# SCH_FCPLCM-2v0_2024-09-18.net
KiCad netlist of a schematic drawn in EasyEDA
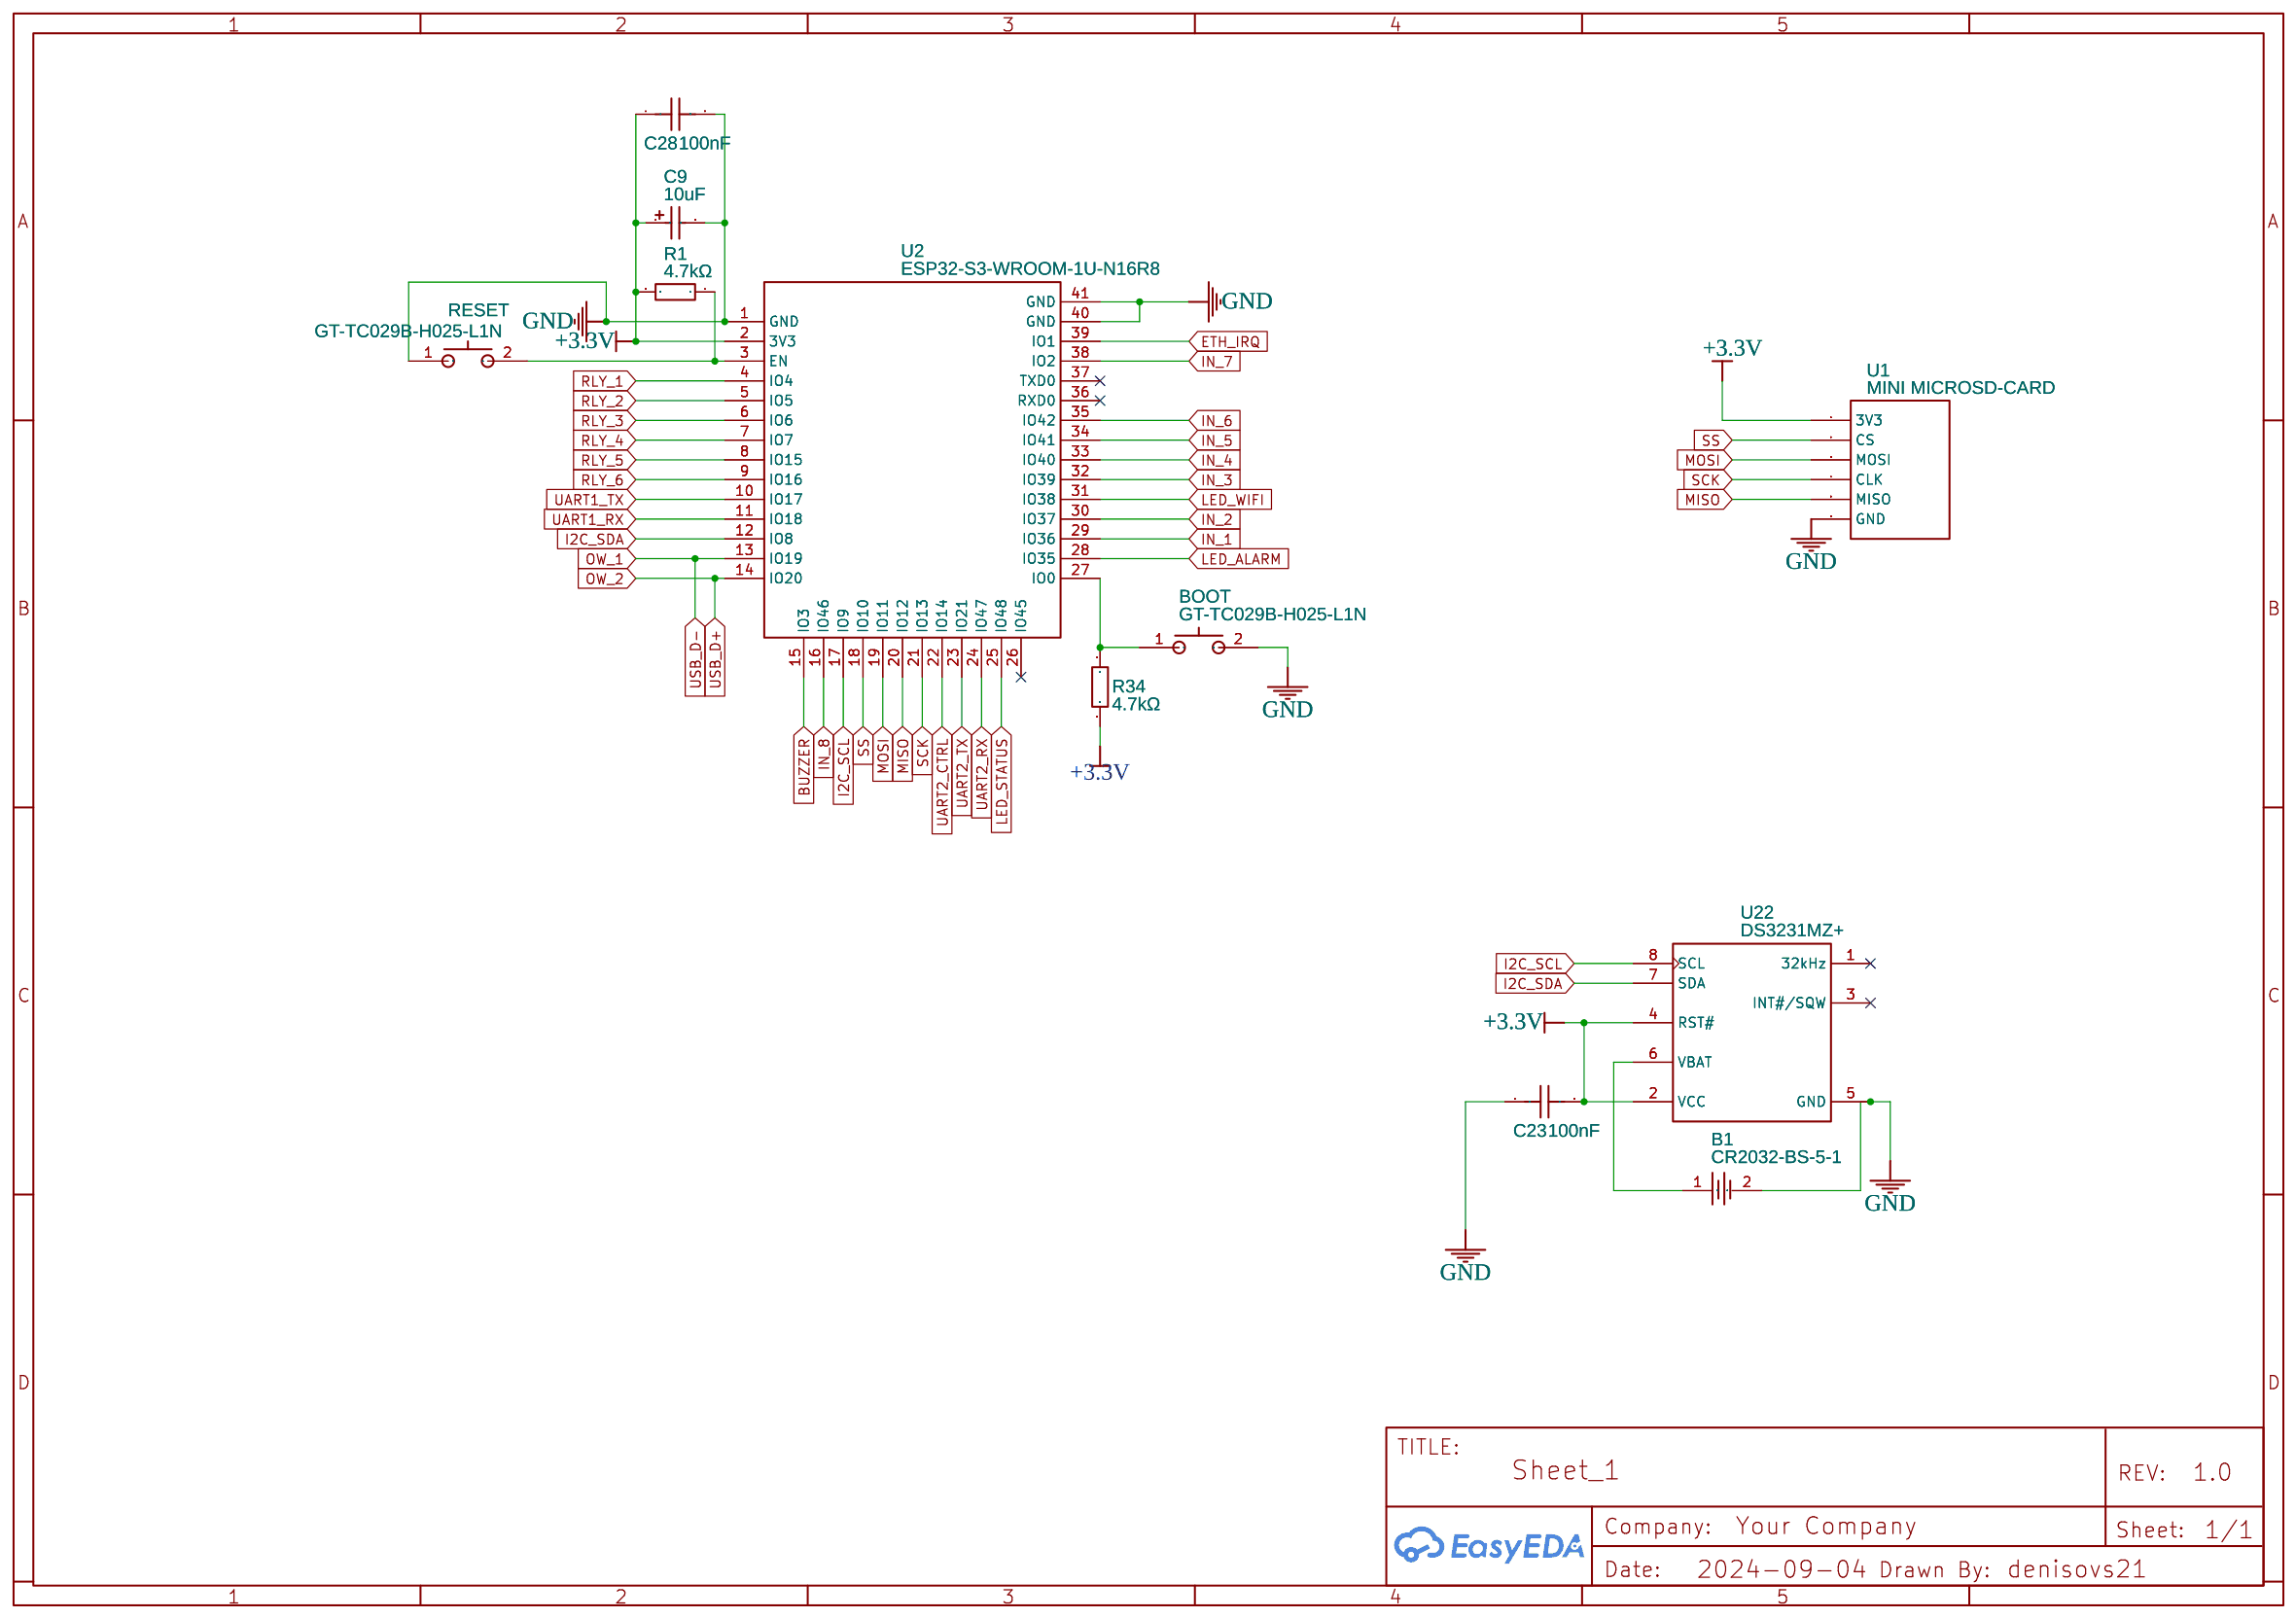
[diagram p0: CPU]
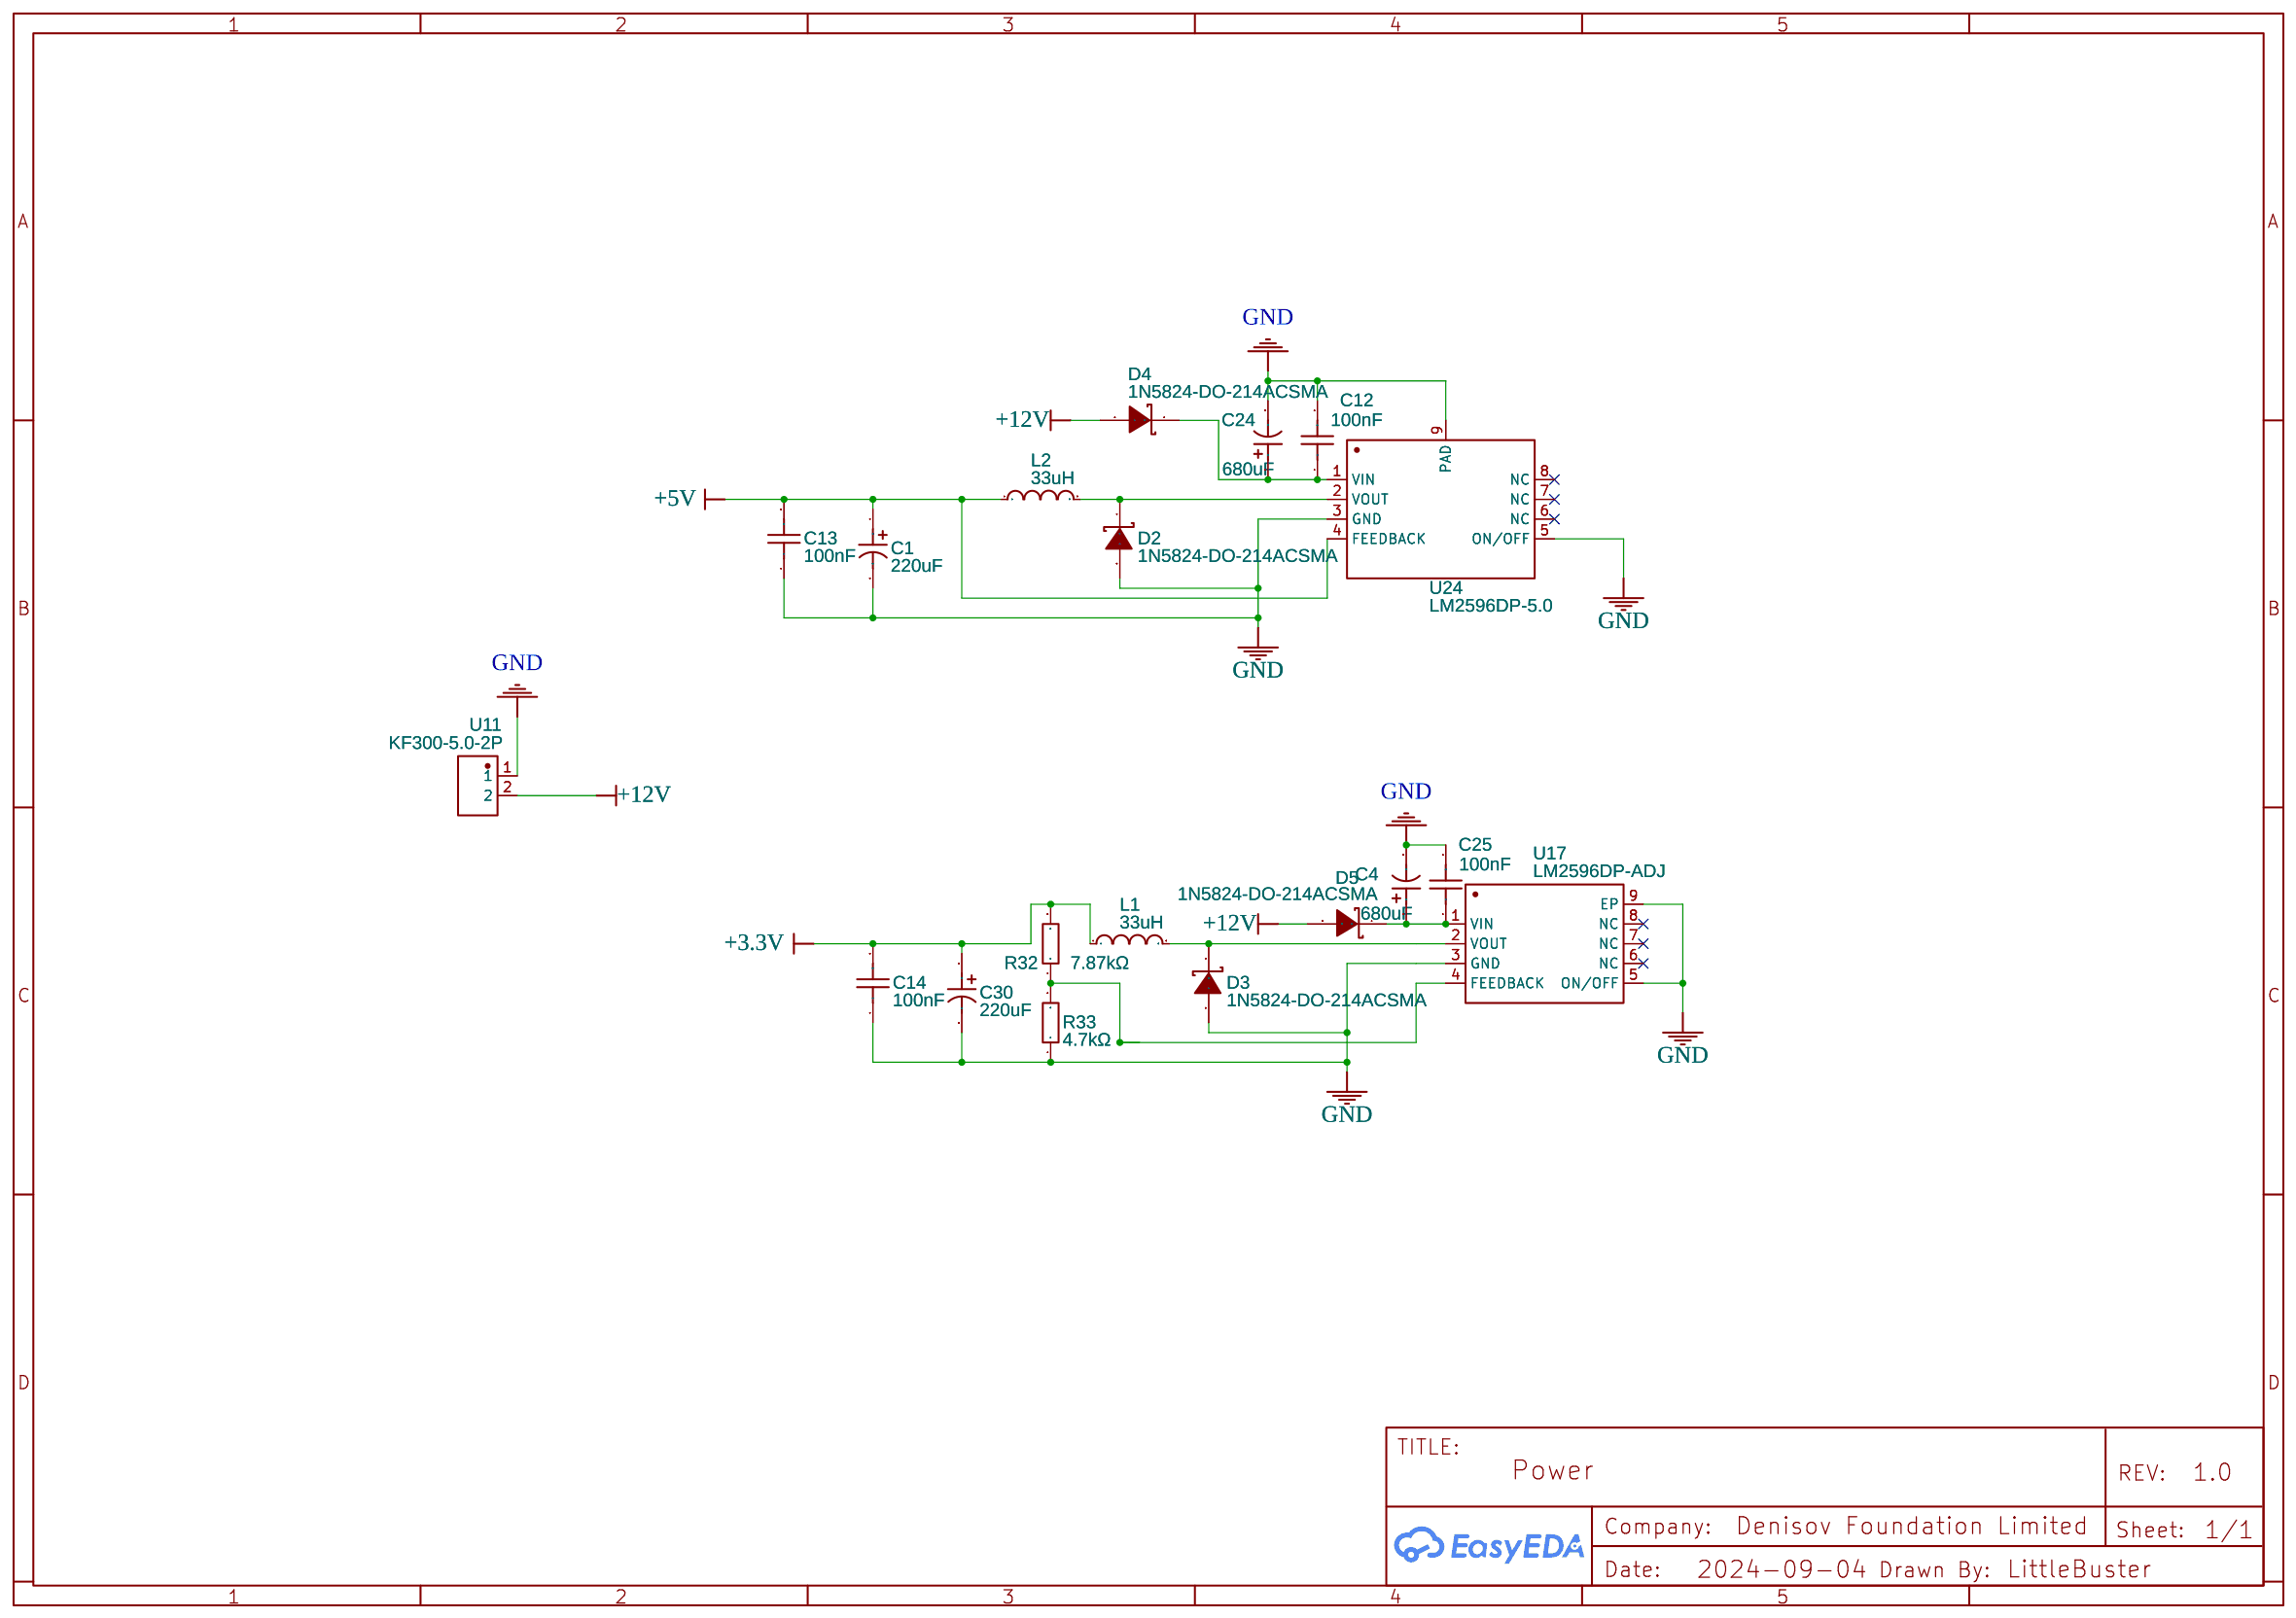
[diagram p1: Power]
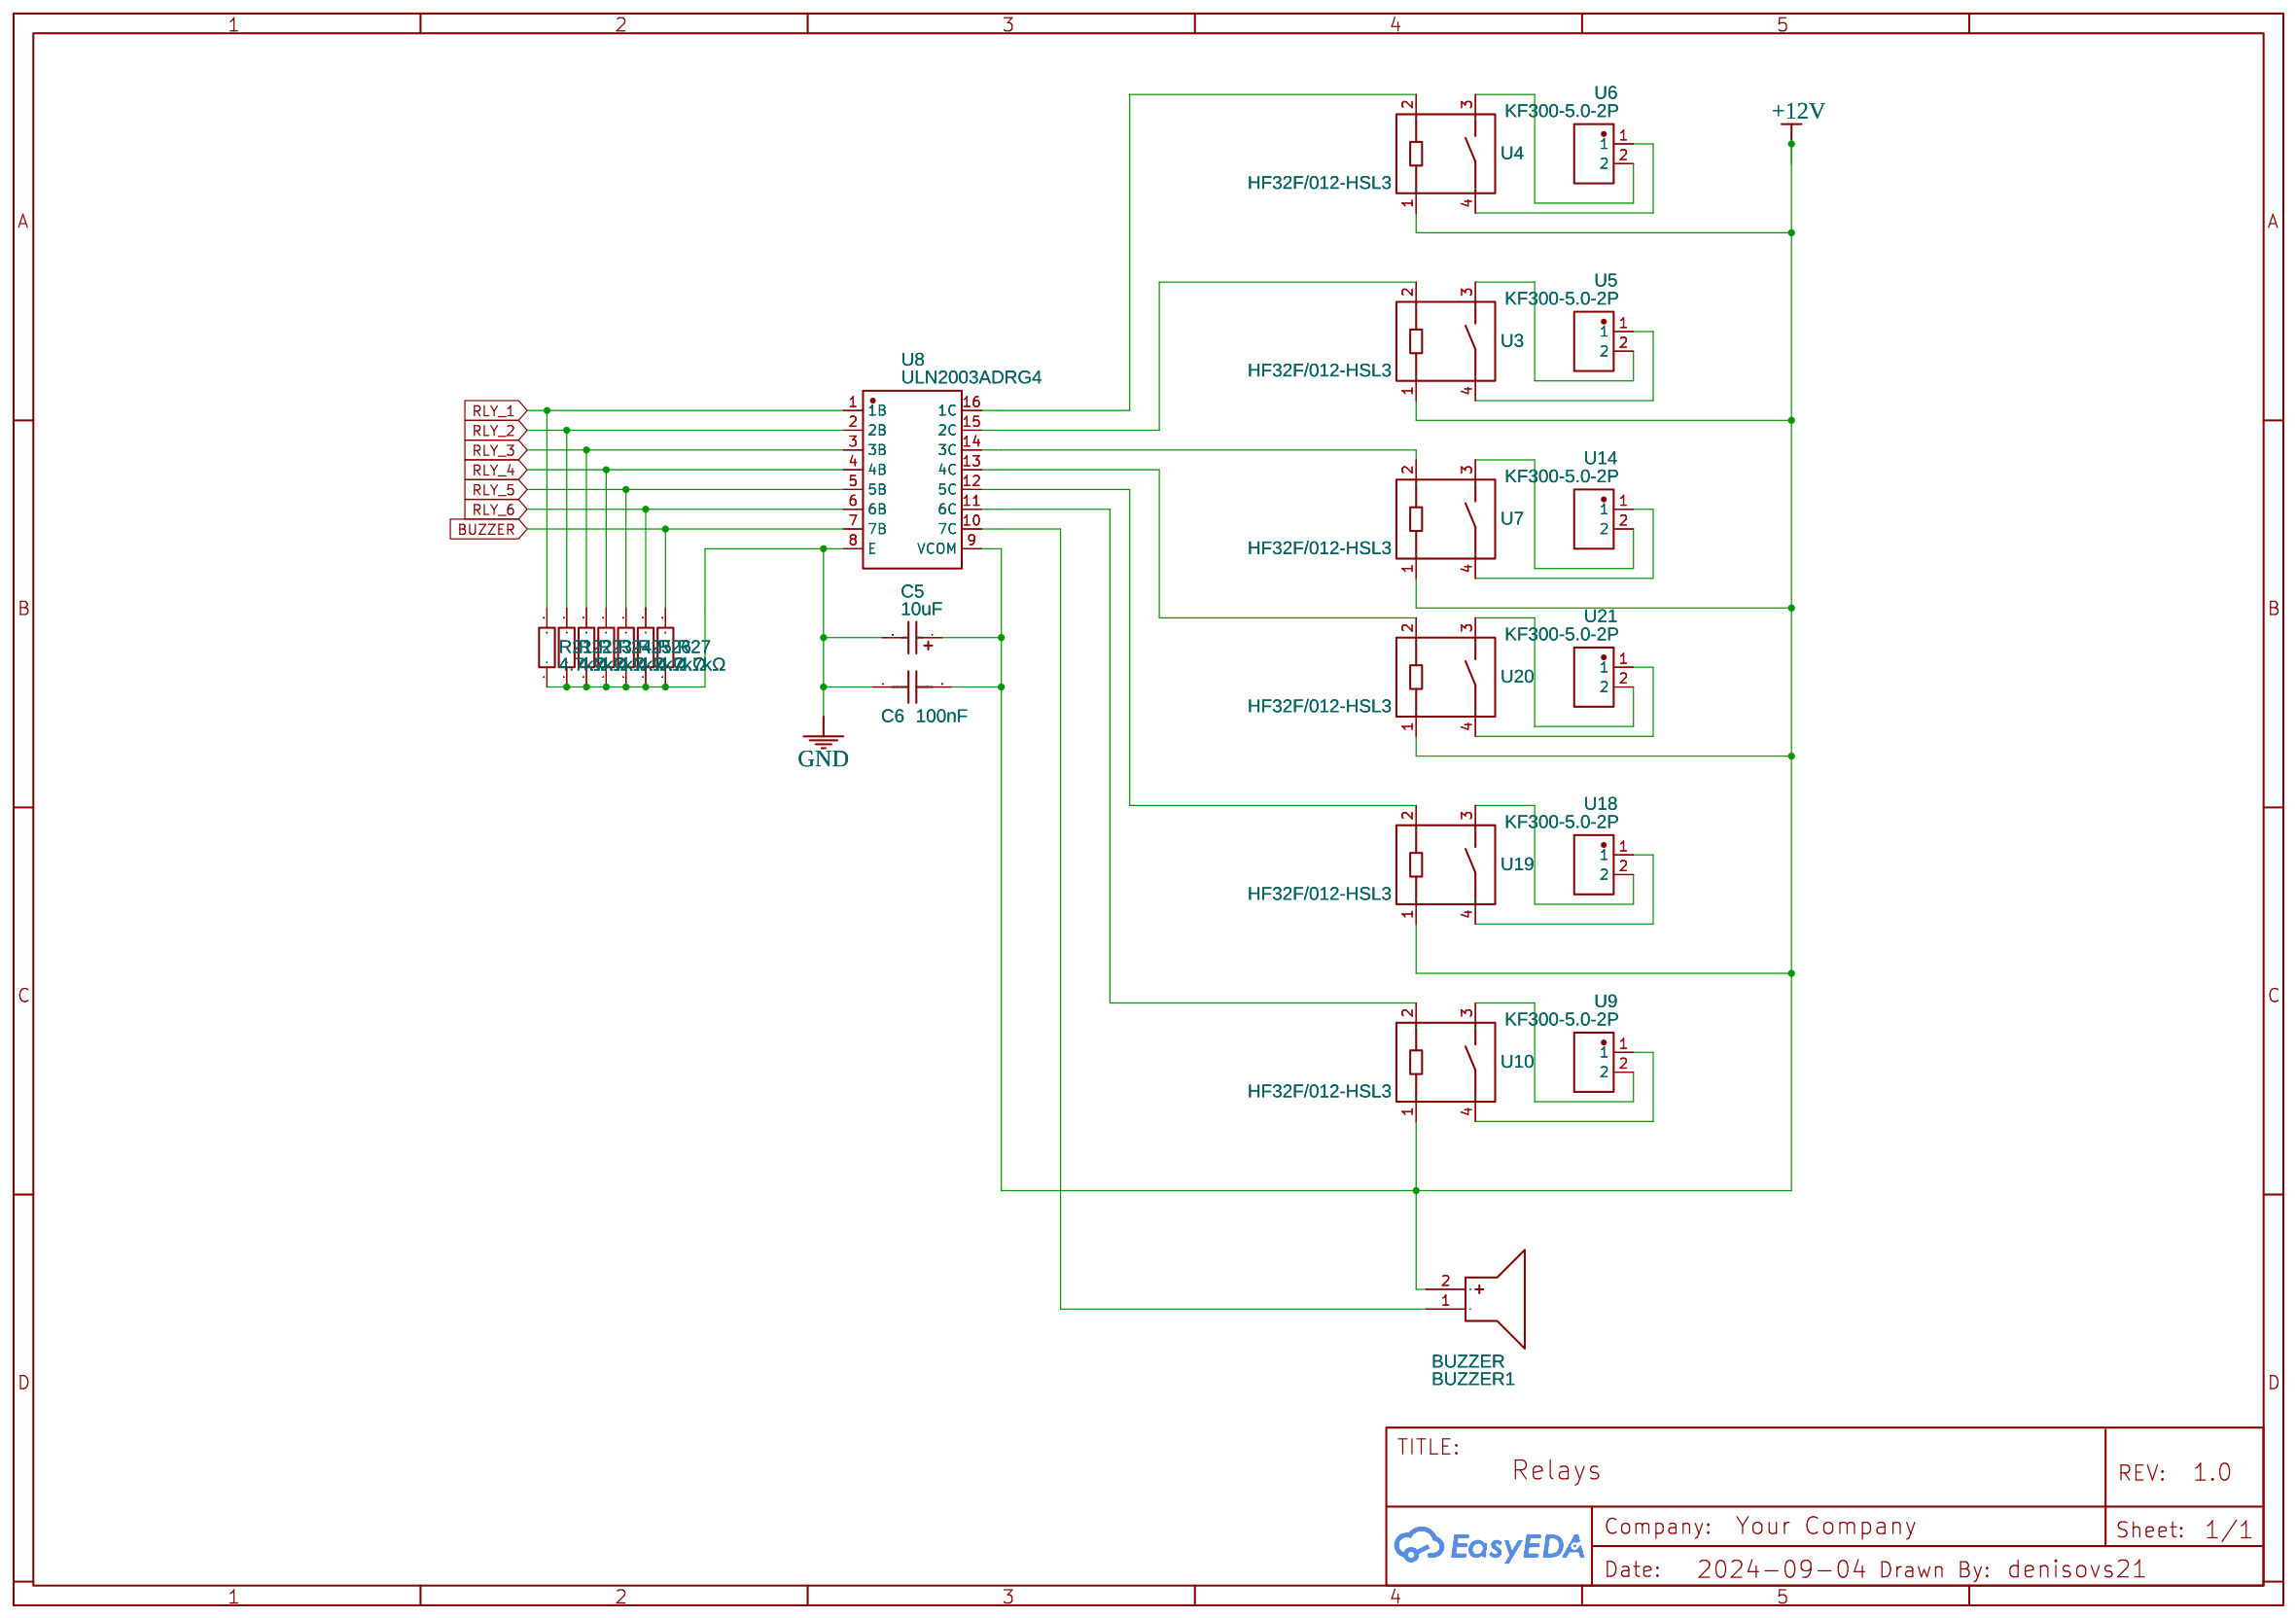
[diagram p2: Relays]
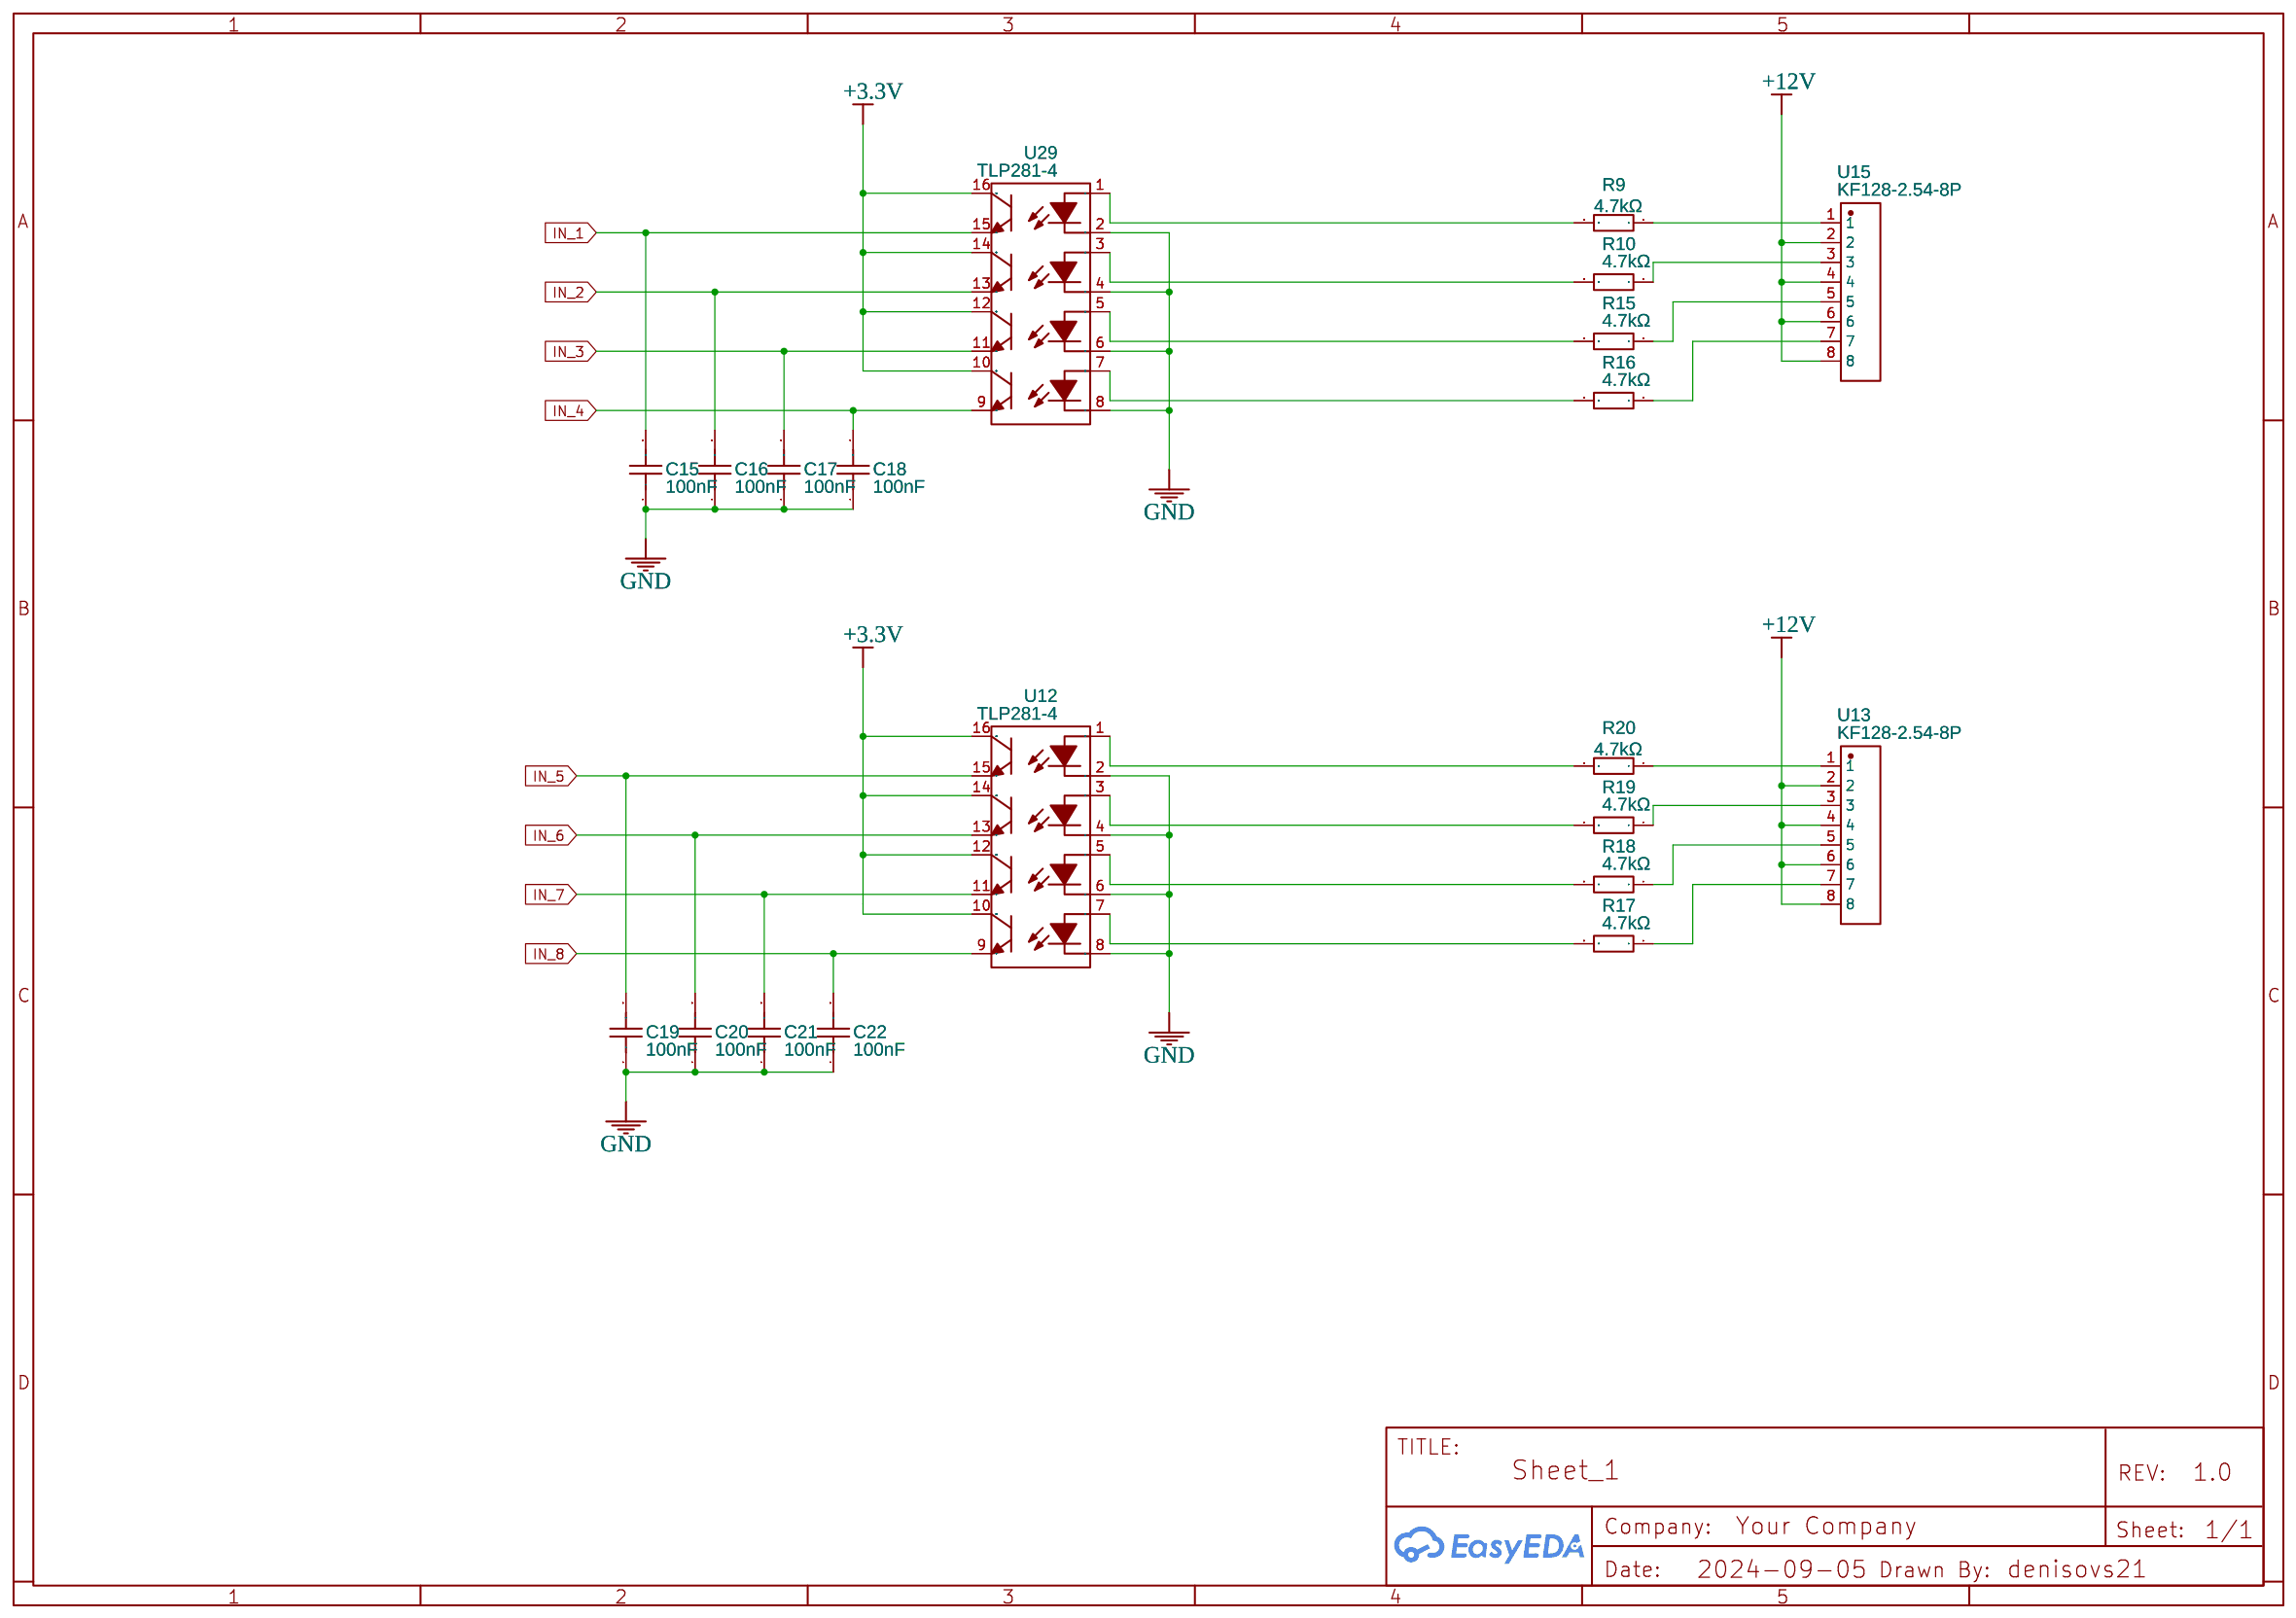
[diagram p3: Inputs]
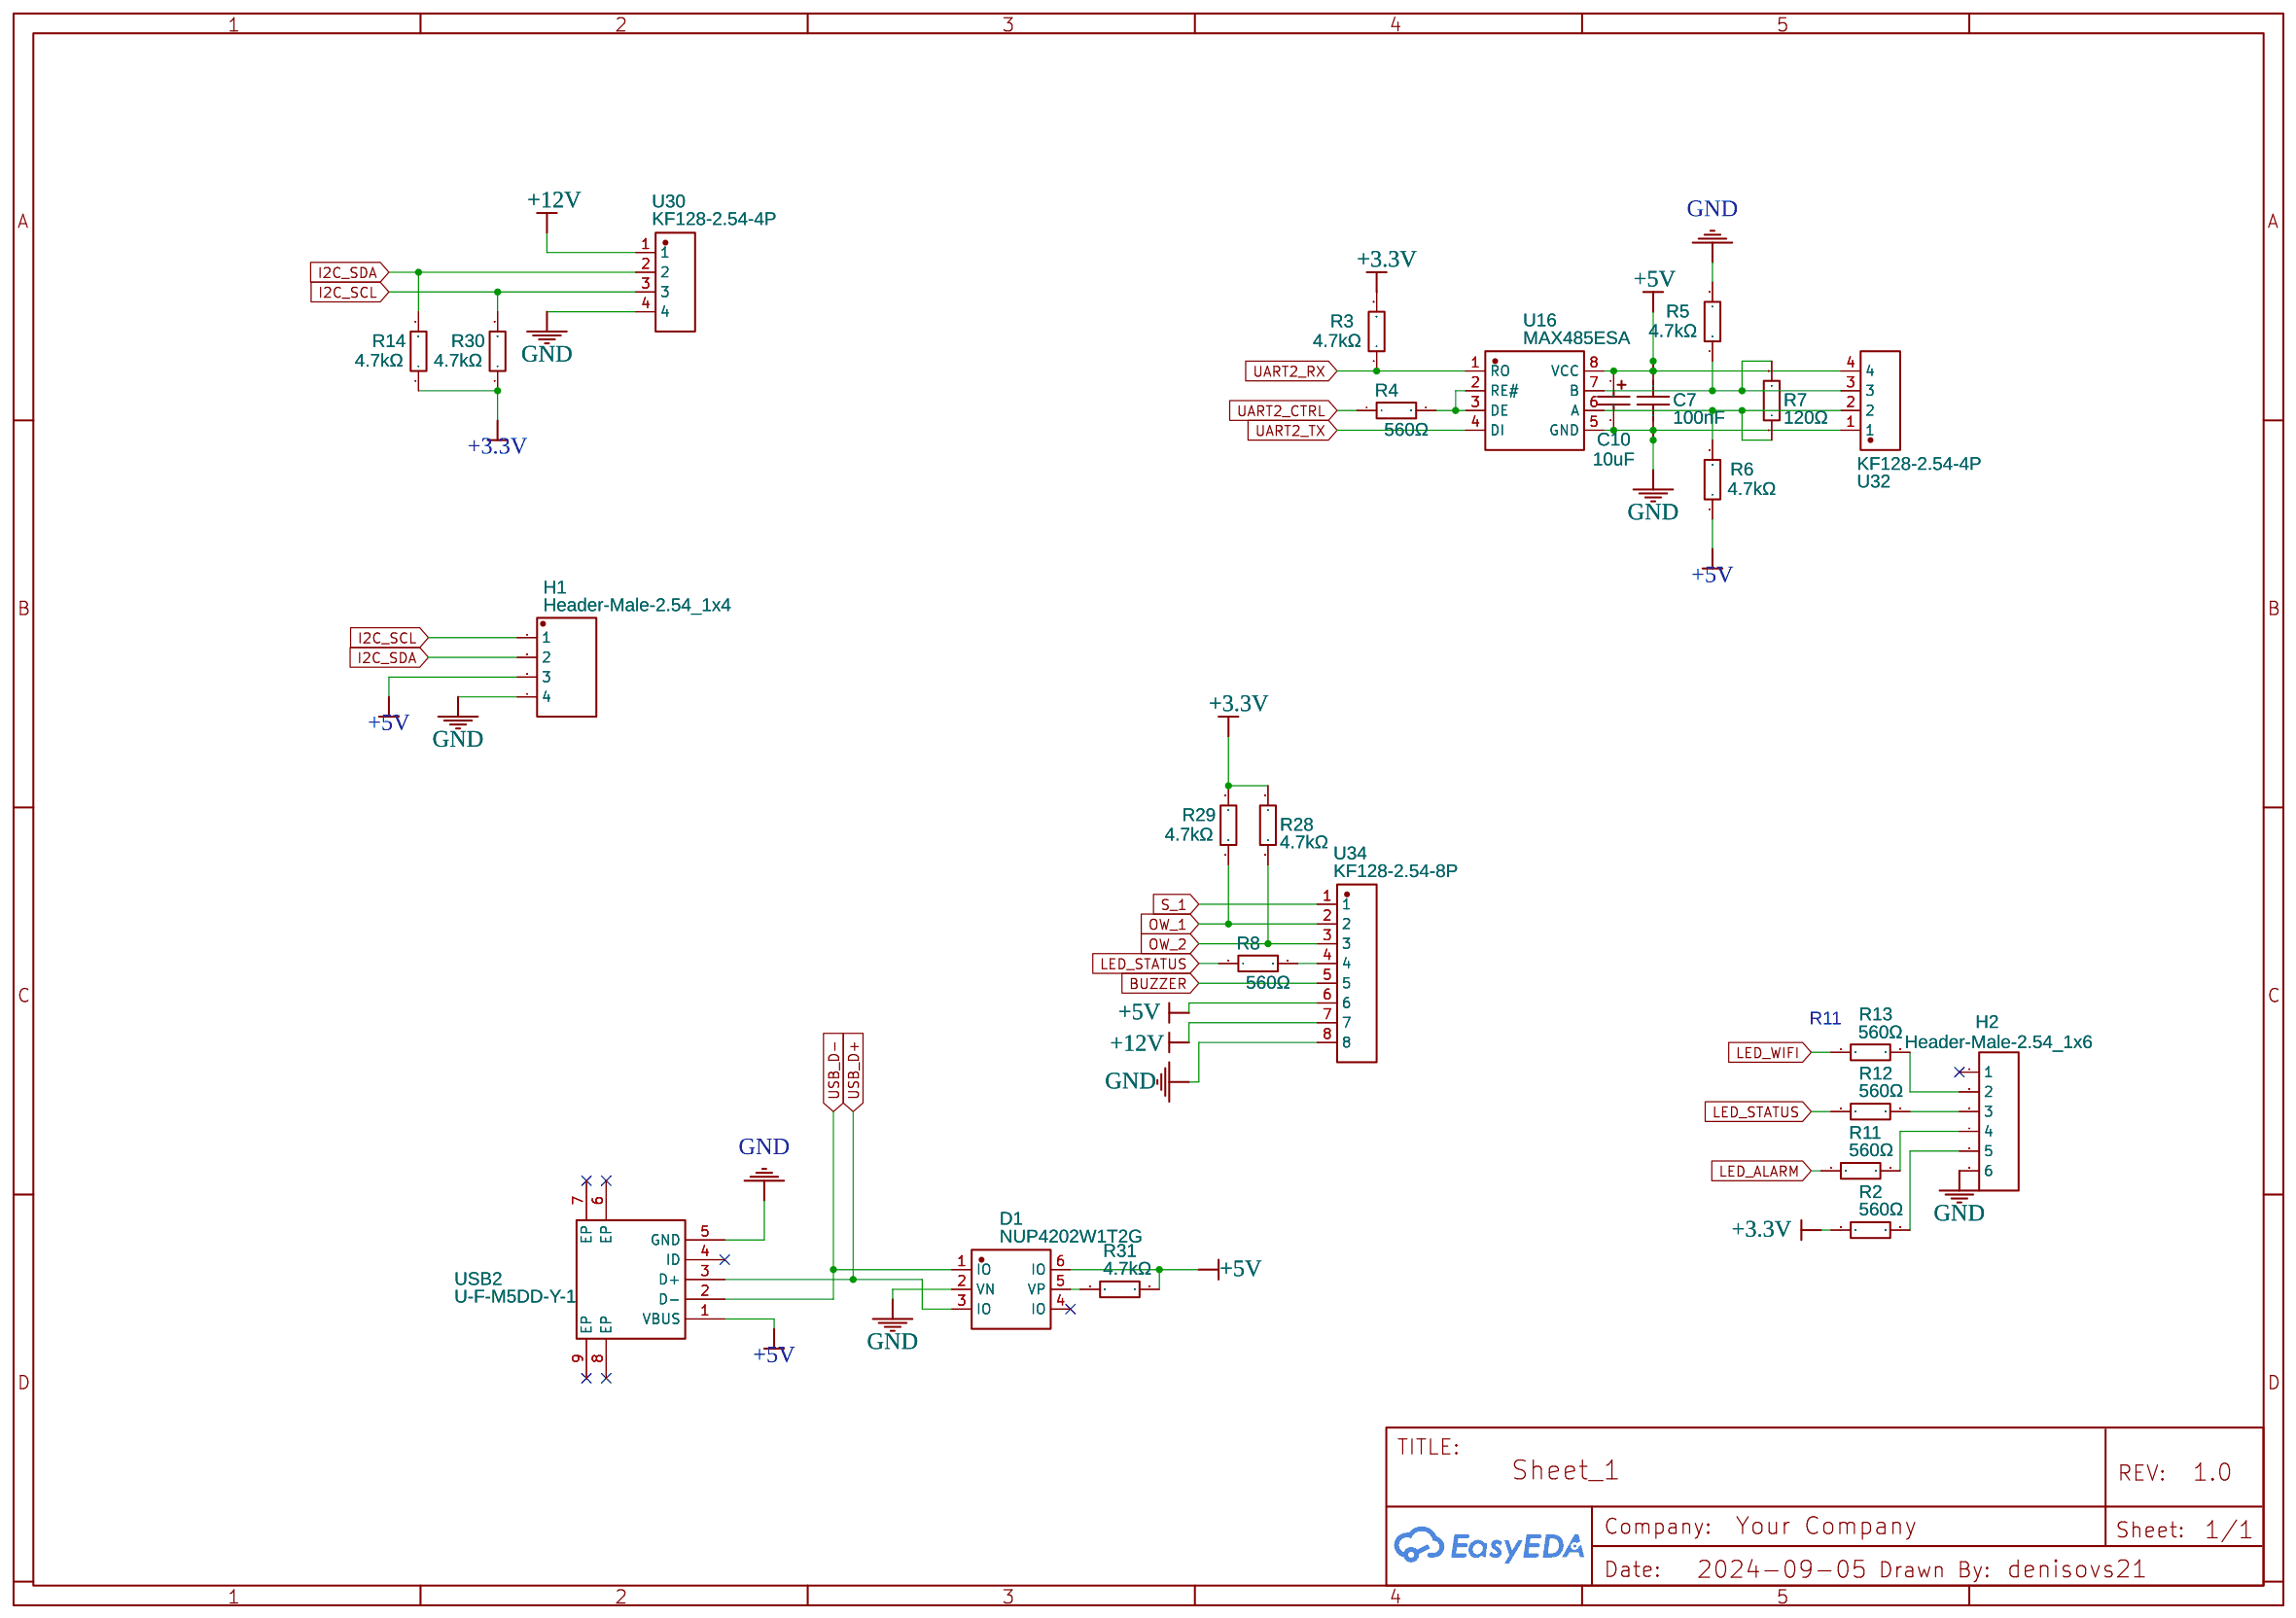
[diagram p4: Peripheral]
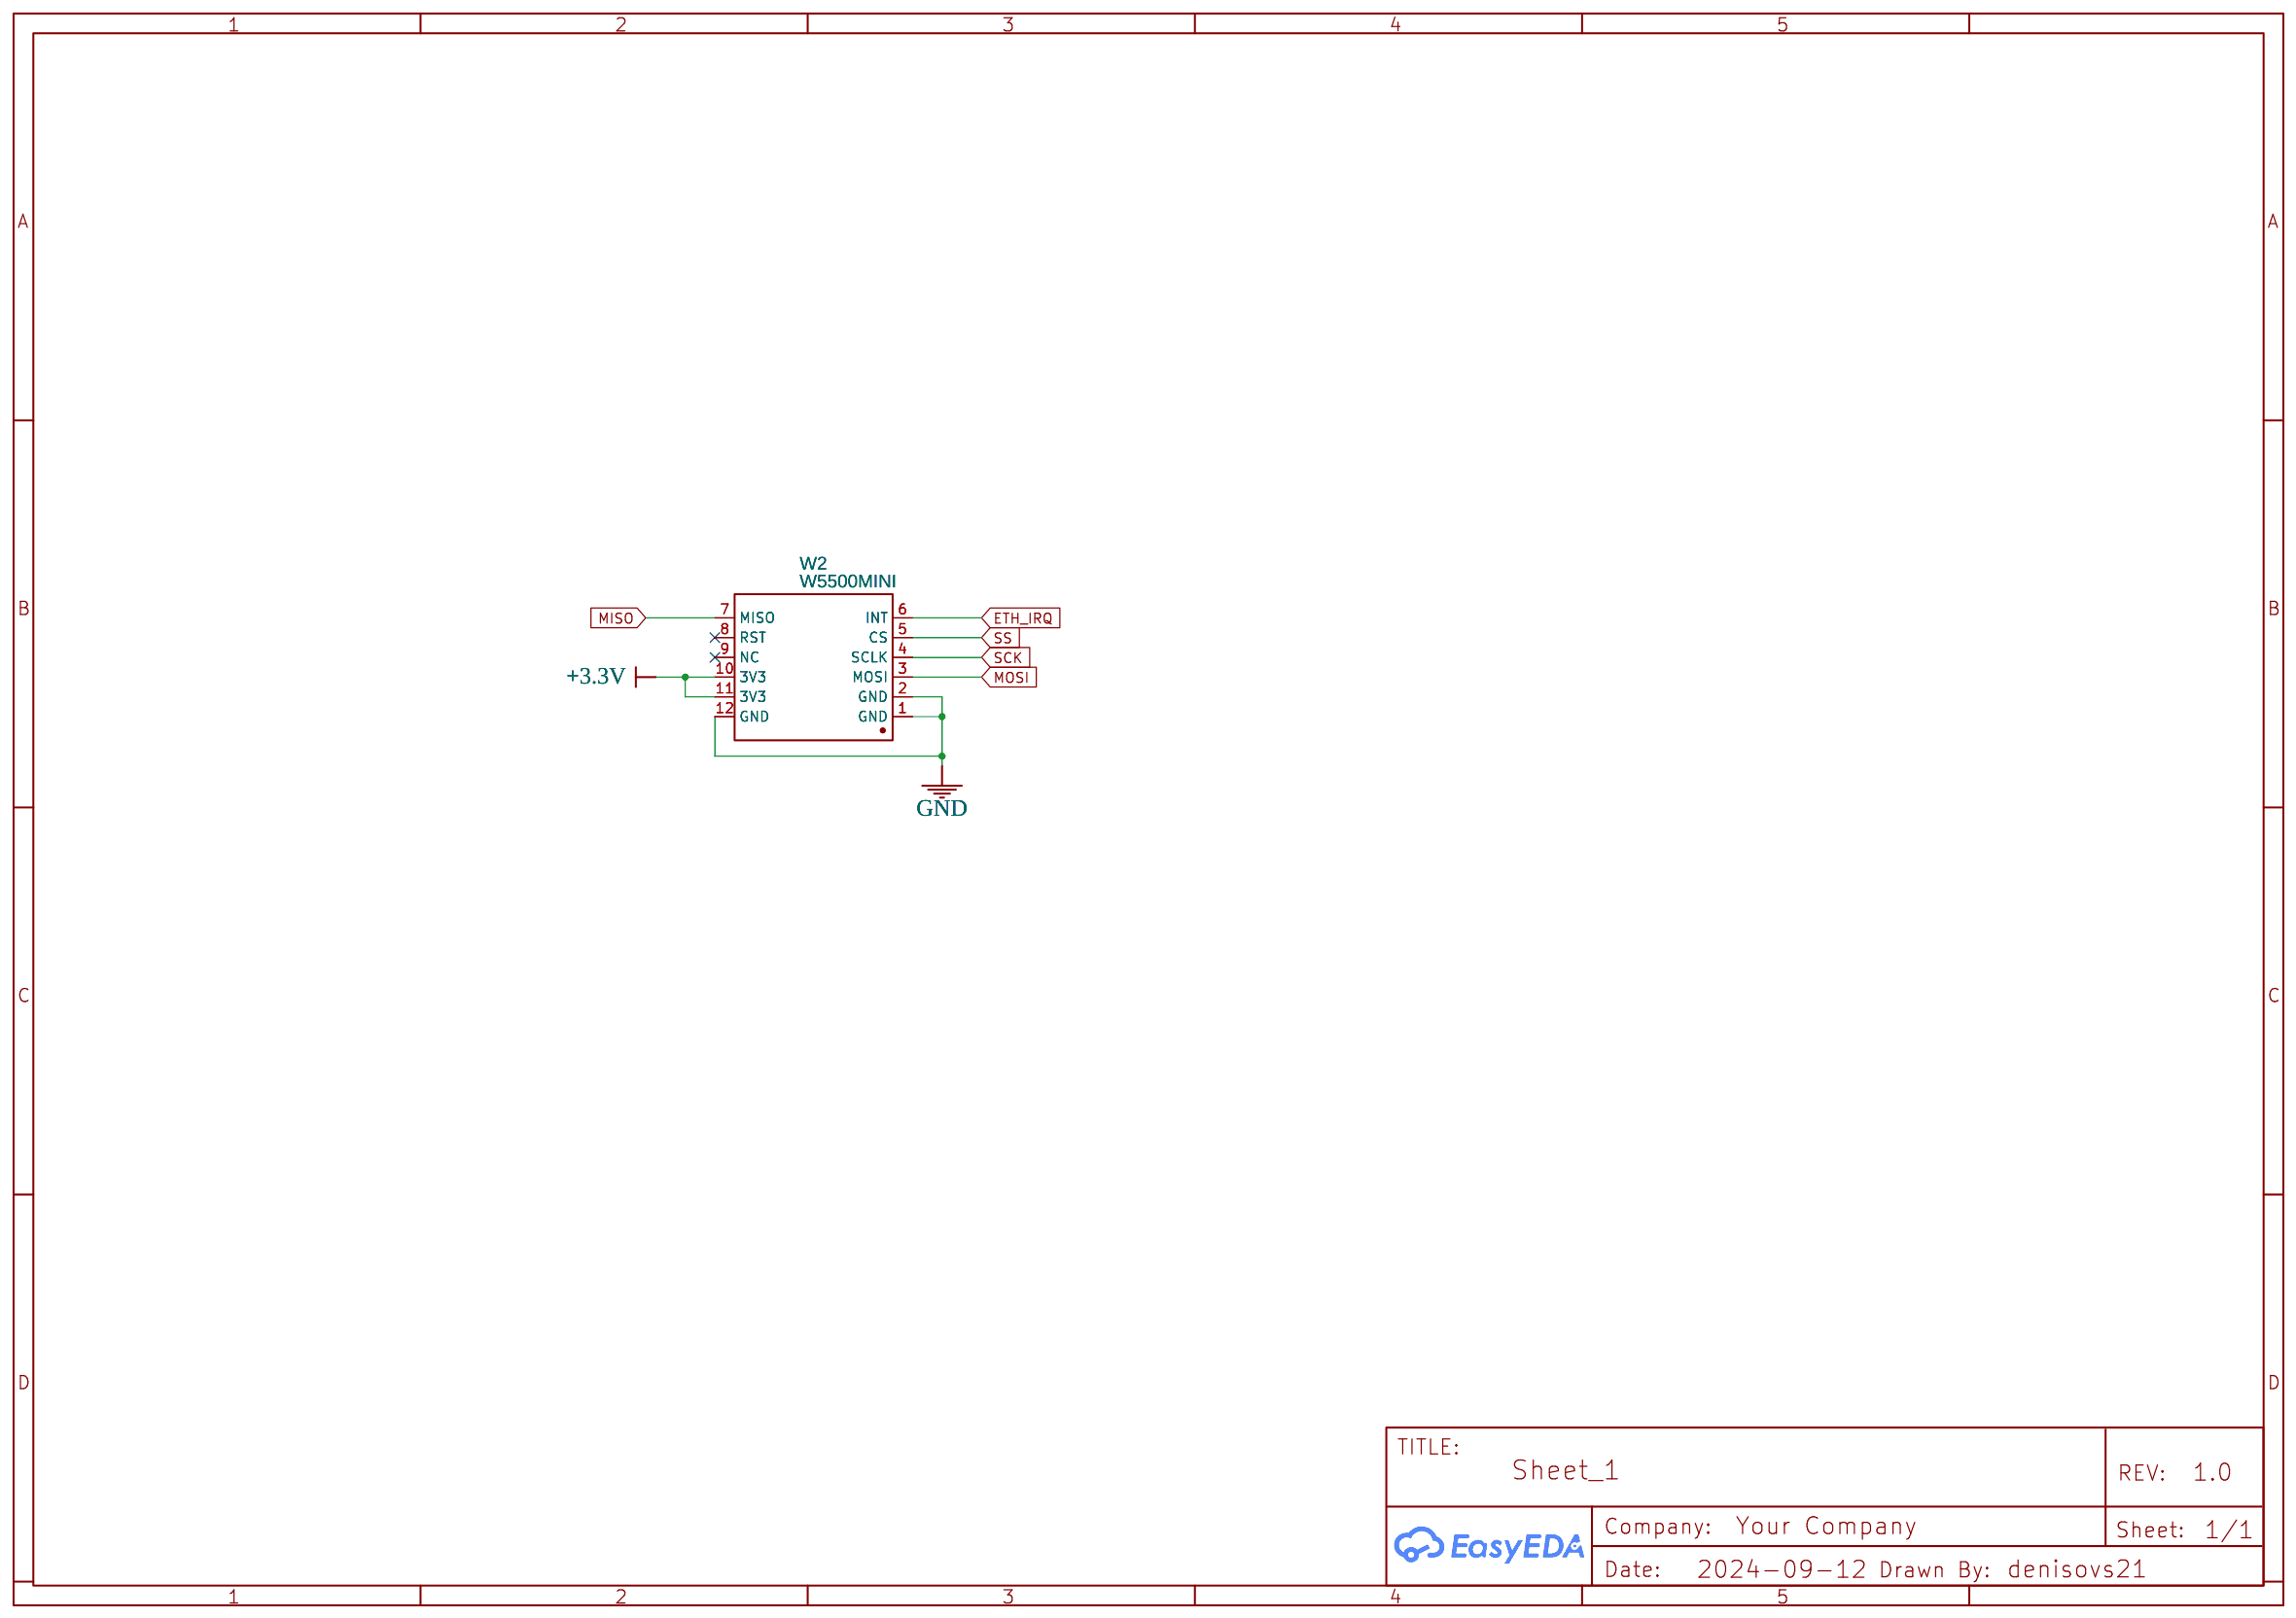
[diagram p5: Ethernet]
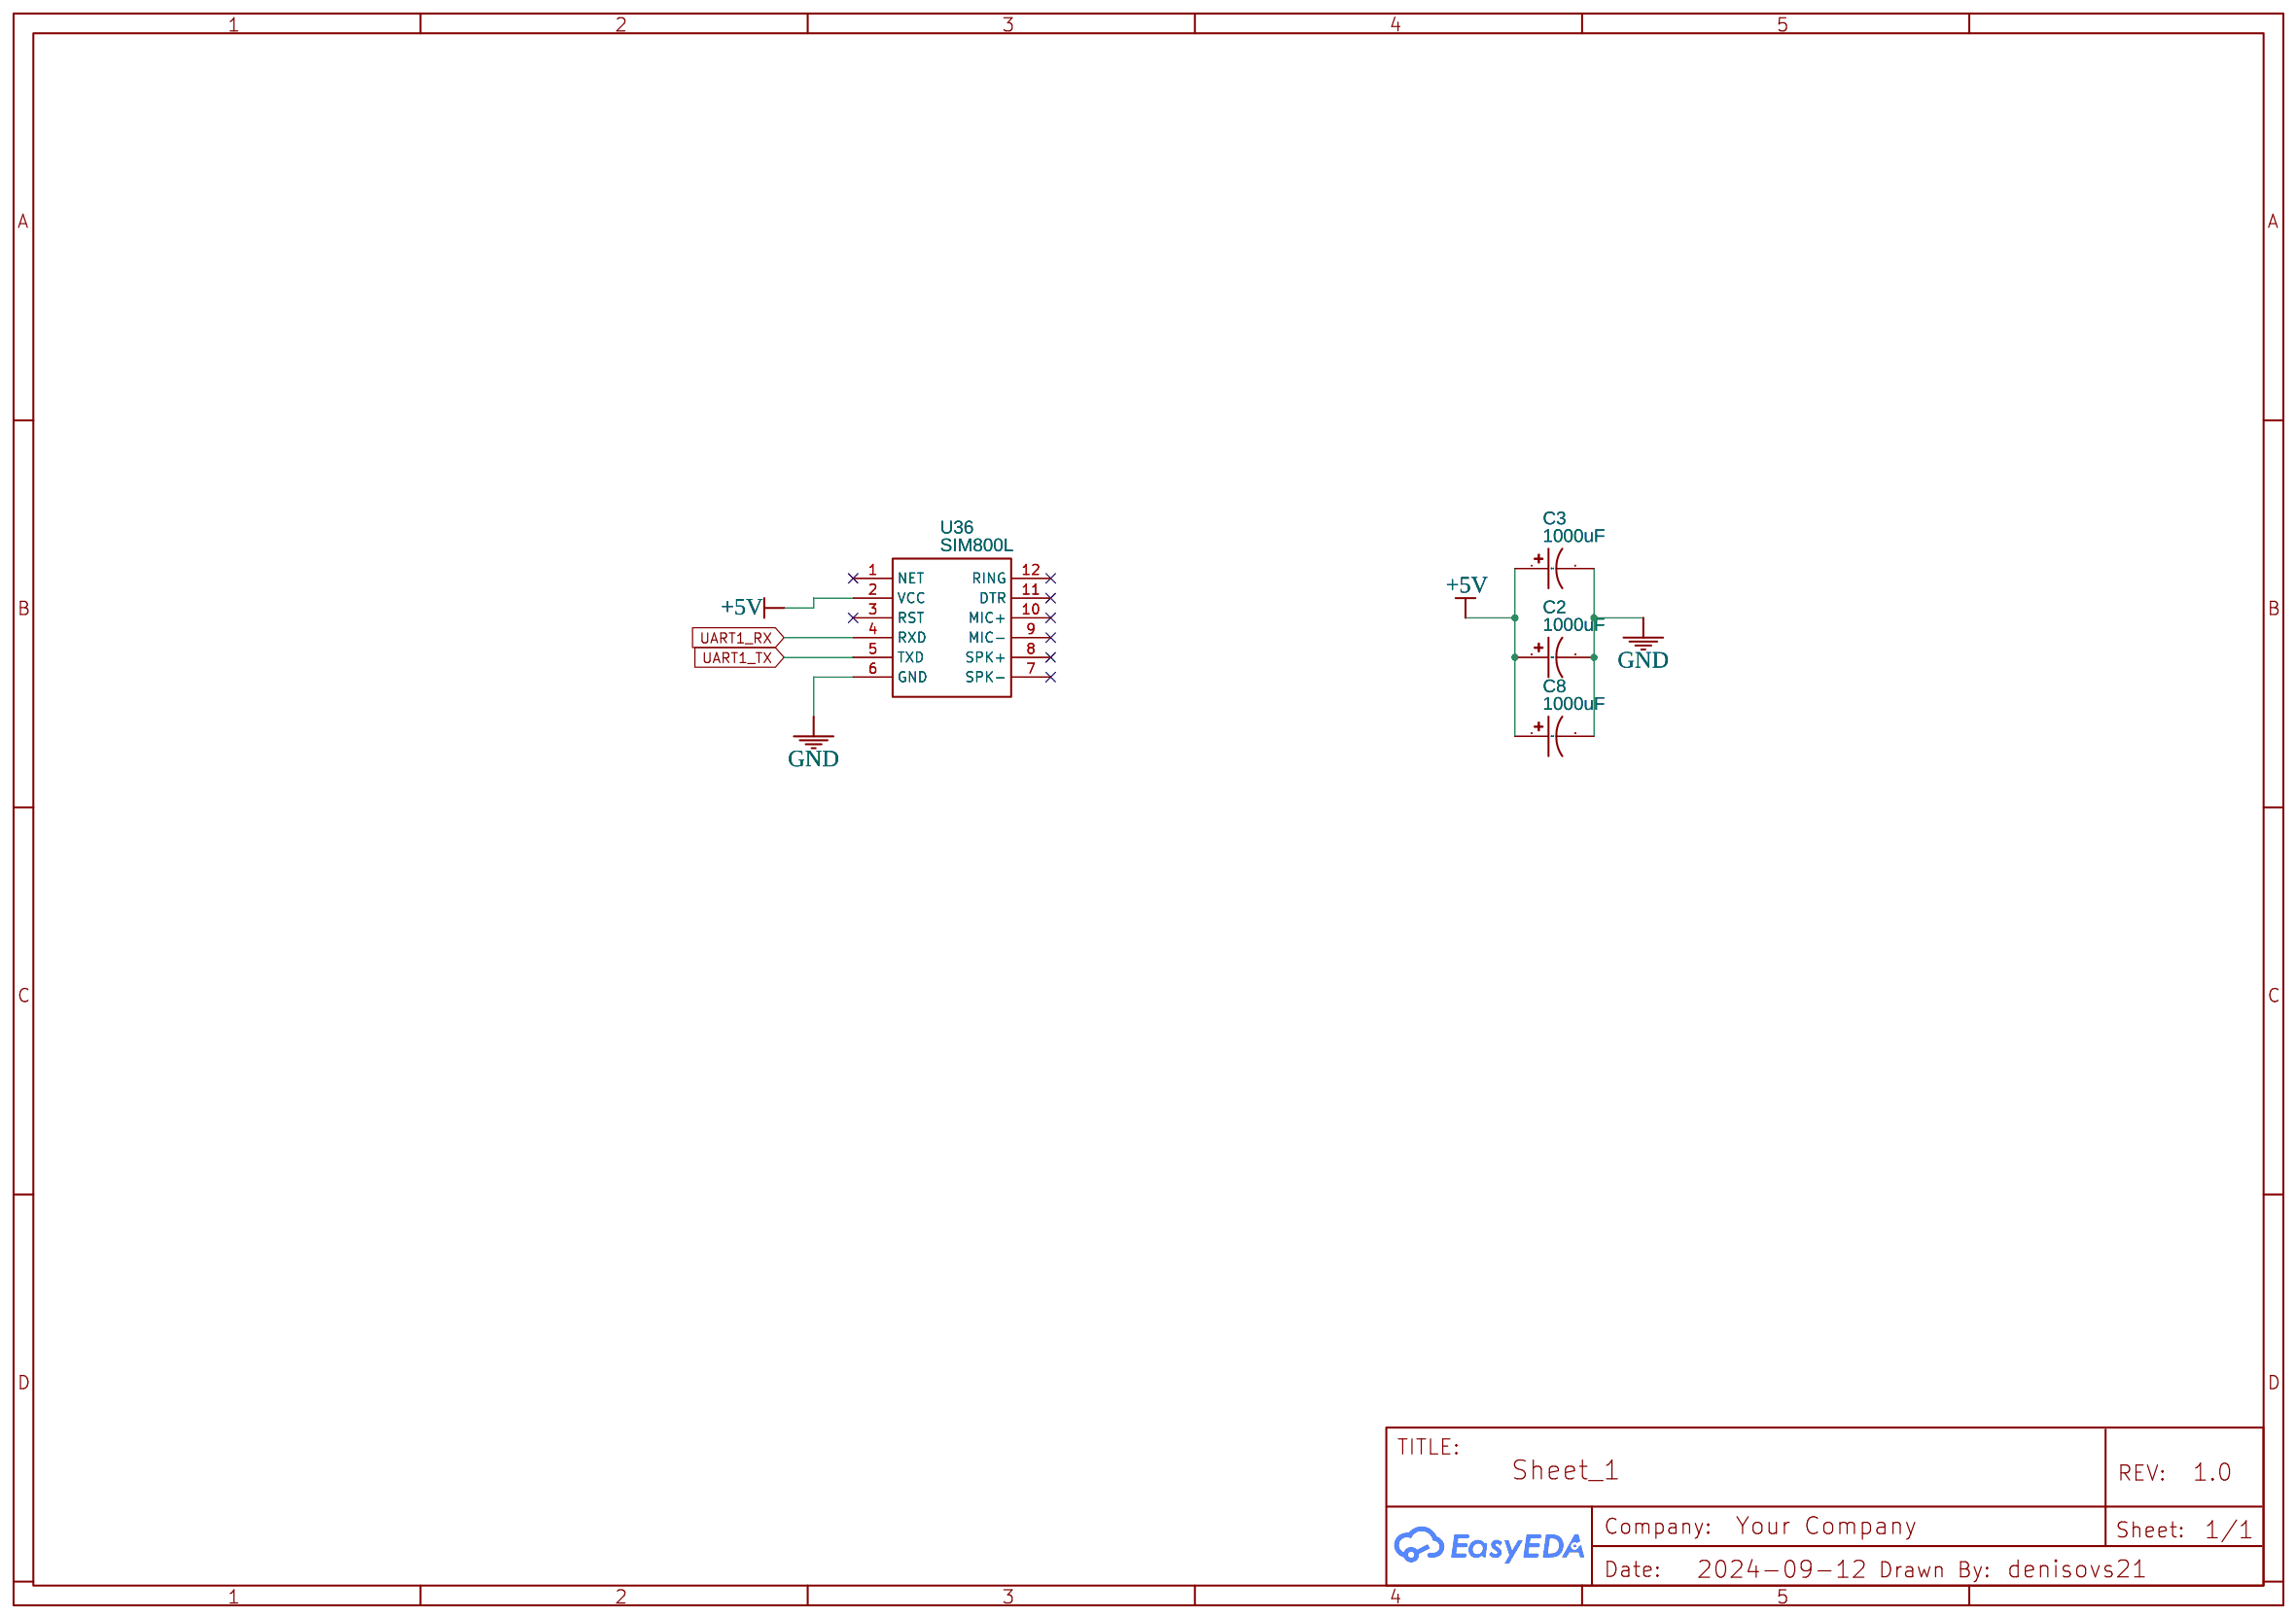
[diagram p6: GSM]

(export (version "E")
  (design (tool "Eeschema 10.0.6"))
  (components
    (comp (ref "B1")
      (value "CR2032-BS-5-1")
      (fields (field (name "Manufacturer") "Q&J"))
      (libsource (lib "") (part "CR2032-BS-5-1"))
    )
    (comp (ref "BOOT")
      (value "GT-TC029B-H025-L1N")
      (fields (field (name "Manufacturer") "G-Switch(品赞)"))
      (libsource (lib "") (part "GT-TC029B-H025-L1N"))
    )
    (comp (ref "C9")
      (value "10uF")
      (fields (field (name "Manufacturer Part") "CA45-B025K106T") (field (name "Manufacturer") "湘怡中元/湘江"))
      (libsource (lib "") (part "CA45-B025K106T"))
    )
    (comp (ref "C23")
      (value "100nF")
      (fields
        (field (name "Manufacturer Part") "CC0805KRX7R7BB104")
        (field (name "Manufacturer") "YAGEO(国巨)")
      )
      (libsource (lib "") (part "CC0805KRX7R7BB104"))
    )
    (comp (ref "C28")
      (value "100nF")
      (fields
        (field (name "Manufacturer Part") "CC0805KRX7R7BB104")
        (field (name "Manufacturer") "YAGEO(国巨)")
      )
      (libsource (lib "") (part "CC0805KRX7R7BB104"))
    )
    (comp (ref "R1")
      (value "4.7kΩ")
      (fields
        (field (name "Manufacturer Part") "0805W8F4701T5E")
        (field (name "Manufacturer") "UNI-ROYAL(厚声)")
      )
      (libsource (lib "") (part "0805W8F4701T5E"))
    )
    (comp (ref "R34")
      (value "4.7kΩ")
      (fields
        (field (name "Manufacturer Part") "0805W8F4701T5E")
        (field (name "Manufacturer") "UNI-ROYAL(厚声)")
      )
      (libsource (lib "") (part "0805W8F4701T5E_1"))
    )
    (comp (ref "RESET")
      (value "GT-TC029B-H025-L1N")
      (fields (field (name "Manufacturer") "G-Switch(品赞)"))
      (libsource (lib "") (part "GT-TC029B-H025-L1N_1"))
    )
    (comp (ref "U1") (value "MINI MICROSD-CARD") (libsource (lib "") (part "MINI MICROSD-CARD")))
    (comp (ref "U2")
      (value "ESP32-S3-WROOM-1U-N16R8")
      (fields (field (name "Manufacturer") "ESPRESSIF(乐鑫)"))
      (libsource (lib "") (part "ESP32-S3-WROOM-1U-N16R8"))
    )
    (comp (ref "U22")
      (value "DS3231MZ+")
      (fields
        (field (name "Manufacturer Part") "DS3231MZ+TRL")
        (field (name "Manufacturer") "ADI(亚德诺)/MAXIM(美信)")
      )
      (libsource (lib "") (part "DS3231MZ+"))
    )
    (comp (ref "C1")
      (value "220uF")
      (fields
        (field (name "Manufacturer Part") "CA45B-B-6.3V-220UF-M")
        (field (name "Manufacturer") "CEC(振华新云)")
      )
      (libsource (lib "") (part "CA45B-B-6.3V-220UF-M"))
    )
    (comp (ref "C4")
      (value "680uF")
      (fields (field (name "Manufacturer Part") "SPT1CM681F12OR") (field (name "Manufacturer") "Yunxing(云星)"))
      (libsource (lib "") (part "SPT1CM681F12OR"))
    )
    (comp (ref "C12")
      (value "100nF")
      (fields
        (field (name "Manufacturer Part") "CC0805KRX7R7BB104")
        (field (name "Manufacturer") "YAGEO(国巨)")
      )
      (libsource (lib "") (part "CC0805KRX7R7BB104"))
    )
    (comp (ref "C13")
      (value "100nF")
      (fields
        (field (name "Manufacturer Part") "CC0805KRX7R7BB104")
        (field (name "Manufacturer") "YAGEO(国巨)")
      )
      (libsource (lib "") (part "CC0805KRX7R7BB104"))
    )
    (comp (ref "C14")
      (value "100nF")
      (fields
        (field (name "Manufacturer Part") "CC0805KRX7R7BB104")
        (field (name "Manufacturer") "YAGEO(国巨)")
      )
      (libsource (lib "") (part "CC0805KRX7R7BB104"))
    )
    (comp (ref "C24")
      (value "680uF")
      (fields (field (name "Manufacturer Part") "SPT1CM681F12OR") (field (name "Manufacturer") "Yunxing(云星)"))
      (libsource (lib "") (part "SPT1CM681F12OR"))
    )
    (comp (ref "C25")
      (value "100nF")
      (fields
        (field (name "Manufacturer Part") "CC0805KRX7R7BB104")
        (field (name "Manufacturer") "YAGEO(国巨)")
      )
      (libsource (lib "") (part "CC0805KRX7R7BB104"))
    )
    (comp (ref "C30")
      (value "220uF")
      (fields
        (field (name "Manufacturer Part") "CA45B-B-6.3V-220UF-M")
        (field (name "Manufacturer") "CEC(振华新云)")
      )
      (libsource (lib "") (part "CA45B-B-6.3V-220UF-M"))
    )
    (comp (ref "D2") (value "1N5824-DO-214ACSMA") (libsource (lib "") (part "1N5824-DO-214ACSMA_1")))
    (comp (ref "D3") (value "1N5824-DO-214ACSMA") (libsource (lib "") (part "1N5824-DO-214ACSMA_1")))
    (comp (ref "D4") (value "1N5824-DO-214ACSMA") (libsource (lib "") (part "1N5824-DO-214ACSMA")))
    (comp (ref "D5") (value "1N5824-DO-214ACSMA") (libsource (lib "") (part "1N5824-DO-214ACSMA")))
    (comp (ref "L1")
      (value "33uH")
      (fields (field (name "Manufacturer Part") "SMMS1040-330M") (field (name "Manufacturer") "SXN(顺翔诺)"))
      (libsource (lib "") (part "SMMS1040-330M"))
    )
    (comp (ref "L2")
      (value "33uH")
      (fields (field (name "Manufacturer Part") "SMMS1040-330M") (field (name "Manufacturer") "SXN(顺翔诺)"))
      (libsource (lib "") (part "SMMS1040-330M"))
    )
    (comp (ref "R32")
      (value "7.87kΩ")
      (fields
        (field (name "Manufacturer Part") "0805W8F7871T5E")
        (field (name "Manufacturer") "UNI-ROYAL(厚声)")
      )
      (libsource (lib "") (part "0805W8F7871T5E"))
    )
    (comp (ref "R33")
      (value "4.7kΩ")
      (fields
        (field (name "Manufacturer Part") "0805W8F4701T5E")
        (field (name "Manufacturer") "UNI-ROYAL(厚声)")
      )
      (libsource (lib "") (part "0805W8F4701T5E"))
    )
    (comp (ref "U11")
      (value "KF300-5.0-2P")
      (fields (field (name "Manufacturer") "KEFA(科发)"))
      (libsource (lib "") (part "KF300-5.0-2P"))
    )
    (comp (ref "U17")
      (value "LM2596DP-ADJ")
      (fields (field (name "Manufacturer") "HTC"))
      (libsource (lib "") (part "LM2596DP-ADJ"))
    )
    (comp (ref "U24")
      (value "LM2596DP-5.0")
      (fields (field (name "Manufacturer") "HTC"))
      (libsource (lib "") (part "LM2596DP-5.0"))
    )
    (comp (ref "BUZZER1")
      (value "BUZZER")
      (fields (field (name "Manufacturer Part") "buzzer"))
      (libsource (lib "") (part "BUZZER"))
    )
    (comp (ref "C5")
      (value "10uF")
      (fields (field (name "Manufacturer Part") "CA45-B025K106T") (field (name "Manufacturer") "湘怡中元/湘江"))
      (libsource (lib "") (part "CA45-B025K106T"))
    )
    (comp (ref "C6")
      (value "100nF")
      (fields
        (field (name "Manufacturer Part") "CC0805KRX7R7BB104")
        (field (name "Manufacturer") "YAGEO(国巨)")
      )
      (libsource (lib "") (part "CC0805KRX7R7BB104"))
    )
    (comp (ref "R21")
      (value "4.7kΩ")
      (fields
        (field (name "Manufacturer Part") "0805W8F4701T5E")
        (field (name "Manufacturer") "UNI-ROYAL(厚声)")
      )
      (libsource (lib "") (part "0805W8F4701T5E"))
    )
    (comp (ref "R22")
      (value "4.7kΩ")
      (fields
        (field (name "Manufacturer Part") "0805W8F4701T5E")
        (field (name "Manufacturer") "UNI-ROYAL(厚声)")
      )
      (libsource (lib "") (part "0805W8F4701T5E"))
    )
    (comp (ref "R23")
      (value "4.7kΩ")
      (fields
        (field (name "Manufacturer Part") "0805W8F4701T5E")
        (field (name "Manufacturer") "UNI-ROYAL(厚声)")
      )
      (libsource (lib "") (part "0805W8F4701T5E"))
    )
    (comp (ref "R24")
      (value "4.7kΩ")
      (fields
        (field (name "Manufacturer Part") "0805W8F4701T5E")
        (field (name "Manufacturer") "UNI-ROYAL(厚声)")
      )
      (libsource (lib "") (part "0805W8F4701T5E"))
    )
    (comp (ref "R25")
      (value "4.7kΩ")
      (fields
        (field (name "Manufacturer Part") "0805W8F4701T5E")
        (field (name "Manufacturer") "UNI-ROYAL(厚声)")
      )
      (libsource (lib "") (part "0805W8F4701T5E"))
    )
    (comp (ref "R26")
      (value "4.7kΩ")
      (fields
        (field (name "Manufacturer Part") "0805W8F4701T5E")
        (field (name "Manufacturer") "UNI-ROYAL(厚声)")
      )
      (libsource (lib "") (part "0805W8F4701T5E"))
    )
    (comp (ref "R27")
      (value "4.7kΩ")
      (fields
        (field (name "Manufacturer Part") "0805W8F4701T5E")
        (field (name "Manufacturer") "UNI-ROYAL(厚声)")
      )
      (libsource (lib "") (part "0805W8F4701T5E"))
    )
    (comp (ref "U3")
      (value "HF32F/012-HSL3")
      (fields (field (name "Manufacturer") "HF(宏发)"))
      (libsource (lib "") (part "HF32F/012-HSL3"))
    )
    (comp (ref "U4")
      (value "HF32F/012-HSL3")
      (fields (field (name "Manufacturer") "HF(宏发)"))
      (libsource (lib "") (part "HF32F/012-HSL3"))
    )
    (comp (ref "U5")
      (value "KF300-5.0-2P")
      (fields (field (name "Manufacturer") "KEFA(科发)"))
      (libsource (lib "") (part "KF300-5.0-2P"))
    )
    (comp (ref "U6")
      (value "KF300-5.0-2P")
      (fields (field (name "Manufacturer") "KEFA(科发)"))
      (libsource (lib "") (part "KF300-5.0-2P"))
    )
    (comp (ref "U7")
      (value "HF32F/012-HSL3")
      (fields (field (name "Manufacturer") "HF(宏发)"))
      (libsource (lib "") (part "HF32F/012-HSL3"))
    )
    (comp (ref "U8") (value "ULN2003ADRG4") (libsource (lib "") (part "ULN2003ADRG4")))
    (comp (ref "U9")
      (value "KF300-5.0-2P")
      (fields (field (name "Manufacturer") "KEFA(科发)"))
      (libsource (lib "") (part "KF300-5.0-2P"))
    )
    (comp (ref "U10")
      (value "HF32F/012-HSL3")
      (fields (field (name "Manufacturer") "HF(宏发)"))
      (libsource (lib "") (part "HF32F/012-HSL3"))
    )
    (comp (ref "U14")
      (value "KF300-5.0-2P")
      (fields (field (name "Manufacturer") "KEFA(科发)"))
      (libsource (lib "") (part "KF300-5.0-2P"))
    )
    (comp (ref "U18")
      (value "KF300-5.0-2P")
      (fields (field (name "Manufacturer") "KEFA(科发)"))
      (libsource (lib "") (part "KF300-5.0-2P"))
    )
    (comp (ref "U19")
      (value "HF32F/012-HSL3")
      (fields (field (name "Manufacturer") "HF(宏发)"))
      (libsource (lib "") (part "HF32F/012-HSL3"))
    )
    (comp (ref "U20")
      (value "HF32F/012-HSL3")
      (fields (field (name "Manufacturer") "HF(宏发)"))
      (libsource (lib "") (part "HF32F/012-HSL3"))
    )
    (comp (ref "U21")
      (value "KF300-5.0-2P")
      (fields (field (name "Manufacturer") "KEFA(科发)"))
      (libsource (lib "") (part "KF300-5.0-2P"))
    )
    (comp (ref "C15")
      (value "100nF")
      (fields
        (field (name "Manufacturer Part") "CC0805KRX7R7BB104")
        (field (name "Manufacturer") "YAGEO(国巨)")
      )
      (libsource (lib "") (part "CC0805KRX7R7BB104"))
    )
    (comp (ref "C16")
      (value "100nF")
      (fields
        (field (name "Manufacturer Part") "CC0805KRX7R7BB104")
        (field (name "Manufacturer") "YAGEO(国巨)")
      )
      (libsource (lib "") (part "CC0805KRX7R7BB104"))
    )
    (comp (ref "C17")
      (value "100nF")
      (fields
        (field (name "Manufacturer Part") "CC0805KRX7R7BB104")
        (field (name "Manufacturer") "YAGEO(国巨)")
      )
      (libsource (lib "") (part "CC0805KRX7R7BB104"))
    )
    (comp (ref "C18")
      (value "100nF")
      (fields
        (field (name "Manufacturer Part") "CC0805KRX7R7BB104")
        (field (name "Manufacturer") "YAGEO(国巨)")
      )
      (libsource (lib "") (part "CC0805KRX7R7BB104"))
    )
    (comp (ref "C19")
      (value "100nF")
      (fields
        (field (name "Manufacturer Part") "CC0805KRX7R7BB104")
        (field (name "Manufacturer") "YAGEO(国巨)")
      )
      (libsource (lib "") (part "CC0805KRX7R7BB104"))
    )
    (comp (ref "C20")
      (value "100nF")
      (fields
        (field (name "Manufacturer Part") "CC0805KRX7R7BB104")
        (field (name "Manufacturer") "YAGEO(国巨)")
      )
      (libsource (lib "") (part "CC0805KRX7R7BB104"))
    )
    (comp (ref "C21")
      (value "100nF")
      (fields
        (field (name "Manufacturer Part") "CC0805KRX7R7BB104")
        (field (name "Manufacturer") "YAGEO(国巨)")
      )
      (libsource (lib "") (part "CC0805KRX7R7BB104"))
    )
    (comp (ref "C22")
      (value "100nF")
      (fields
        (field (name "Manufacturer Part") "CC0805KRX7R7BB104")
        (field (name "Manufacturer") "YAGEO(国巨)")
      )
      (libsource (lib "") (part "CC0805KRX7R7BB104"))
    )
    (comp (ref "R9")
      (value "4.7kΩ")
      (fields
        (field (name "Manufacturer Part") "0805W8F4701T5E")
        (field (name "Manufacturer") "UNI-ROYAL(厚声)")
      )
      (libsource (lib "") (part "0805W8F4701T5E"))
    )
    (comp (ref "R10")
      (value "4.7kΩ")
      (fields
        (field (name "Manufacturer Part") "0805W8F4701T5E")
        (field (name "Manufacturer") "UNI-ROYAL(厚声)")
      )
      (libsource (lib "") (part "0805W8F4701T5E"))
    )
    (comp (ref "R15")
      (value "4.7kΩ")
      (fields
        (field (name "Manufacturer Part") "0805W8F4701T5E")
        (field (name "Manufacturer") "UNI-ROYAL(厚声)")
      )
      (libsource (lib "") (part "0805W8F4701T5E"))
    )
    (comp (ref "R16")
      (value "4.7kΩ")
      (fields
        (field (name "Manufacturer Part") "0805W8F4701T5E")
        (field (name "Manufacturer") "UNI-ROYAL(厚声)")
      )
      (libsource (lib "") (part "0805W8F4701T5E"))
    )
    (comp (ref "R17")
      (value "4.7kΩ")
      (fields
        (field (name "Manufacturer Part") "0805W8F4701T5E")
        (field (name "Manufacturer") "UNI-ROYAL(厚声)")
      )
      (libsource (lib "") (part "0805W8F4701T5E"))
    )
    (comp (ref "R18")
      (value "4.7kΩ")
      (fields
        (field (name "Manufacturer Part") "0805W8F4701T5E")
        (field (name "Manufacturer") "UNI-ROYAL(厚声)")
      )
      (libsource (lib "") (part "0805W8F4701T5E"))
    )
    (comp (ref "R19")
      (value "4.7kΩ")
      (fields
        (field (name "Manufacturer Part") "0805W8F4701T5E")
        (field (name "Manufacturer") "UNI-ROYAL(厚声)")
      )
      (libsource (lib "") (part "0805W8F4701T5E"))
    )
    (comp (ref "R20")
      (value "4.7kΩ")
      (fields
        (field (name "Manufacturer Part") "0805W8F4701T5E")
        (field (name "Manufacturer") "UNI-ROYAL(厚声)")
      )
      (libsource (lib "") (part "0805W8F4701T5E"))
    )
    (comp (ref "U12")
      (value "TLP281-4")
      (fields (field (name "Manufacturer") "ISOCOM(英国安数光)"))
      (libsource (lib "") (part "TLP281-4"))
    )
    (comp (ref "U13")
      (value "KF128-2.54-8P")
      (fields (field (name "Manufacturer") "KEFA(科发)"))
      (libsource (lib "") (part "KF128-2.54-8P"))
    )
    (comp (ref "U15")
      (value "KF128-2.54-8P")
      (fields (field (name "Manufacturer") "KEFA(科发)"))
      (libsource (lib "") (part "KF128-2.54-8P"))
    )
    (comp (ref "U29")
      (value "TLP281-4")
      (fields (field (name "Manufacturer") "ISOCOM(英国安数光)"))
      (libsource (lib "") (part "TLP281-4"))
    )
    (comp (ref "C7")
      (value "100nF")
      (fields
        (field (name "Manufacturer Part") "CC0805KRX7R7BB104")
        (field (name "Manufacturer") "YAGEO(国巨)")
      )
      (libsource (lib "") (part "CC0805KRX7R7BB104"))
    )
    (comp (ref "C10")
      (value "10uF")
      (fields (field (name "Manufacturer Part") "CA45-B025K106T") (field (name "Manufacturer") "湘怡中元/湘江"))
      (libsource (lib "") (part "CA45-B025K106T"))
    )
    (comp (ref "D1")
      (value "NUP4202W1T2G")
      (fields (field (name "Manufacturer") "onsemi(安森美)"))
      (libsource (lib "") (part "NUP4202W1T2G"))
    )
    (comp (ref "H1")
      (value "Header-Male-2.54_1x4")
      (fields (field (name "Manufacturer Part") "B-2100S04P-A110") (field (name "Manufacturer") "Ckmtw(灿科盟)"))
      (libsource (lib "") (part "Header-Male-2.54_1x4"))
    )
    (comp (ref "H2")
      (value "Header-Male-2.54_1x6")
      (fields (field (name "Manufacturer Part") "2.54-1x6P直针") (field (name "Manufacturer") "BOOMELE(博穆精密)"))
      (libsource (lib "") (part "Header-Male-2.54_1x6"))
    )
    (comp (ref "R2")
      (value "560Ω")
      (fields
        (field (name "Manufacturer Part") "0805W8F5600T5E")
        (field (name "Manufacturer") "UNI-ROYAL(厚声)")
      )
      (libsource (lib "") (part "0805W8F5600T5E"))
    )
    (comp (ref "R3")
      (value "4.7kΩ")
      (fields
        (field (name "Manufacturer Part") "0805W8F4701T5E")
        (field (name "Manufacturer") "UNI-ROYAL(厚声)")
      )
      (libsource (lib "") (part "0805W8F4701T5E"))
    )
    (comp (ref "R4")
      (value "560Ω")
      (fields
        (field (name "Manufacturer Part") "0805W8F5600T5E")
        (field (name "Manufacturer") "UNI-ROYAL(厚声)")
      )
      (libsource (lib "") (part "0805W8F5600T5E"))
    )
    (comp (ref "R5")
      (value "4.7kΩ")
      (fields
        (field (name "Manufacturer Part") "0805W8F4701T5E")
        (field (name "Manufacturer") "UNI-ROYAL(厚声)")
      )
      (libsource (lib "") (part "0805W8F4701T5E"))
    )
    (comp (ref "R6")
      (value "4.7kΩ")
      (fields
        (field (name "Manufacturer Part") "0805W8F4701T5E")
        (field (name "Manufacturer") "UNI-ROYAL(厚声)")
      )
      (libsource (lib "") (part "0805W8F4701T5E"))
    )
    (comp (ref "R7")
      (value "120Ω")
      (fields (field (name "Manufacturer Part") "ARG05FTC1200") (field (name "Manufacturer") "Viking(光颉)"))
      (libsource (lib "") (part "ARG05FTC1200"))
    )
    (comp (ref "R8")
      (value "560Ω")
      (fields
        (field (name "Manufacturer Part") "0805W8F5600T5E")
        (field (name "Manufacturer") "UNI-ROYAL(厚声)")
      )
      (libsource (lib "") (part "0805W8F5600T5E"))
    )
    (comp (ref "R11")
      (value "560Ω")
      (fields
        (field (name "Manufacturer Part") "0805W8F5600T5E")
        (field (name "Manufacturer") "UNI-ROYAL(厚声)")
      )
      (libsource (lib "") (part "0805W8F5600T5E"))
    )
    (comp (ref "R12")
      (value "560Ω")
      (fields
        (field (name "Manufacturer Part") "0805W8F5600T5E")
        (field (name "Manufacturer") "UNI-ROYAL(厚声)")
      )
      (libsource (lib "") (part "0805W8F5600T5E"))
    )
    (comp (ref "R13")
      (value "560Ω")
      (fields
        (field (name "Manufacturer Part") "0805W8F5600T5E")
        (field (name "Manufacturer") "UNI-ROYAL(厚声)")
      )
      (libsource (lib "") (part "0805W8F5600T5E"))
    )
    (comp (ref "R14")
      (value "4.7kΩ")
      (fields
        (field (name "Manufacturer Part") "0805W8F4701T5E")
        (field (name "Manufacturer") "UNI-ROYAL(厚声)")
      )
      (libsource (lib "") (part "0805W8F4701T5E"))
    )
    (comp (ref "R28")
      (value "4.7kΩ")
      (fields
        (field (name "Manufacturer Part") "0805W8F4701T5E")
        (field (name "Manufacturer") "UNI-ROYAL(厚声)")
      )
      (libsource (lib "") (part "0805W8F4701T5E"))
    )
    (comp (ref "R29")
      (value "4.7kΩ")
      (fields
        (field (name "Manufacturer Part") "0805W8F4701T5E")
        (field (name "Manufacturer") "UNI-ROYAL(厚声)")
      )
      (libsource (lib "") (part "0805W8F4701T5E"))
    )
    (comp (ref "R30")
      (value "4.7kΩ")
      (fields
        (field (name "Manufacturer Part") "0805W8F4701T5E")
        (field (name "Manufacturer") "UNI-ROYAL(厚声)")
      )
      (libsource (lib "") (part "0805W8F4701T5E"))
    )
    (comp (ref "R31")
      (value "4.7kΩ")
      (fields
        (field (name "Manufacturer Part") "0805W8F4701T5E")
        (field (name "Manufacturer") "UNI-ROYAL(厚声)")
      )
      (libsource (lib "") (part "0805W8F4701T5E_1"))
    )
    (comp (ref "U16")
      (value "MAX485ESA")
      (fields (field (name "Manufacturer Part") "max485ESA") (field (name "Manufacturer") "JSMSEMI(杰盛微)"))
      (libsource (lib "") (part "MAX485ESA"))
    )
    (comp (ref "U30")
      (value "KF128-2.54-4P")
      (fields (field (name "Manufacturer") "KEFA(科发)"))
      (libsource (lib "") (part "KF128-2.54-4P"))
    )
    (comp (ref "U32")
      (value "KF128-2.54-4P")
      (fields (field (name "Manufacturer") "KEFA(科发)"))
      (libsource (lib "") (part "KF128-2.54-4P_1"))
    )
    (comp (ref "U34")
      (value "KF128-2.54-8P")
      (fields (field (name "Manufacturer") "KEFA(科发)"))
      (libsource (lib "") (part "KF128-2.54-8P"))
    )
    (comp (ref "USB2")
      (value "U-F-M5DD-Y-1")
      (fields (field (name "Manufacturer") "韩国韩荣"))
      (libsource (lib "") (part "U-F-M5DD-Y-1"))
    )
    (comp (ref "W2") (value "W5500MINI") (libsource (lib "") (part "W5500MINI")))
    (comp (ref "C2")
      (value "1000uF")
      (fields (field (name "Manufacturer Part") "50PZE68MT78X9") (field (name "Manufacturer") "rubycon(红宝石)"))
      (libsource (lib "") (part "50PZE68MT78X9"))
    )
    (comp (ref "C3")
      (value "1000uF")
      (fields (field (name "Manufacturer Part") "50PZE68MT78X9") (field (name "Manufacturer") "rubycon(红宝石)"))
      (libsource (lib "") (part "50PZE68MT78X9"))
    )
    (comp (ref "C8")
      (value "1000uF")
      (fields (field (name "Manufacturer Part") "50PZE68MT78X9") (field (name "Manufacturer") "rubycon(红宝石)"))
      (libsource (lib "") (part "50PZE68MT78X9"))
    )
    (comp (ref "U36") (value "SIM800L") (libsource (lib "") (part "SIM800L")))
  )
  (nets
    (net (code "1") (name "+3.3V") (class "Default")
      (node (ref "C14") (pin "2") (pinfunction "2_2") (pintype "unspecified"))
      (node (ref "C23") (pin "2") (pinfunction "2_2") (pintype "unspecified"))
      (node (ref "C28") (pin "1") (pinfunction "1_1") (pintype "unspecified"))
      (node (ref "C30") (pin "1") (pinfunction "1_1") (pintype "input"))
      (node (ref "C9") (pin "1") (pinfunction "1_1") (pintype "input"))
      (node (ref "L1") (pin "1") (pinfunction "1_1") (pintype "unspecified"))
      (node (ref "R1") (pin "2") (pinfunction "2_2") (pintype "input"))
      (node (ref "R14") (pin "1") (pinfunction "1_1") (pintype "input"))
      (node (ref "R2") (pin "1") (pinfunction "1_1") (pintype "input"))
      (node (ref "R28") (pin "2") (pinfunction "2_2") (pintype "input"))
      (node (ref "R29") (pin "2") (pinfunction "2_2") (pintype "input"))
      (node (ref "R3") (pin "2") (pinfunction "2_2") (pintype "input"))
      (node (ref "R30") (pin "1") (pinfunction "1_1") (pintype "input"))
      (node (ref "R32") (pin "2") (pinfunction "2_2") (pintype "input"))
      (node (ref "R34") (pin "2") (pinfunction "2_2") (pintype "input"))
      (node (ref "U1") (pin "1") (pinfunction "3V3_1") (pintype "unspecified"))
      (node (ref "U12") (pin "10") (pinfunction "COL_10") (pintype "unspecified"))
      (node (ref "U12") (pin "12") (pinfunction "COL_12") (pintype "unspecified"))
      (node (ref "U12") (pin "14") (pinfunction "COL_14") (pintype "unspecified"))
      (node (ref "U12") (pin "16") (pinfunction "COL_16") (pintype "unspecified"))
      (node (ref "U2") (pin "2") (pinfunction "3V3_2") (pintype "passive"))
      (node (ref "U22") (pin "2") (pinfunction "VCC_2") (pintype "passive"))
      (node (ref "U22") (pin "4") (pinfunction "RST#_4") (pintype "bidirectional"))
      (node (ref "U29") (pin "10") (pinfunction "COL_10") (pintype "unspecified"))
      (node (ref "U29") (pin "12") (pinfunction "COL_12") (pintype "unspecified"))
      (node (ref "U29") (pin "14") (pinfunction "COL_14") (pintype "unspecified"))
      (node (ref "U29") (pin "16") (pinfunction "COL_16") (pintype "unspecified"))
      (node (ref "W2") (pin "10") (pinfunction "3V3_10") (pintype "unspecified"))
      (node (ref "W2") (pin "11") (pinfunction "3V3_11") (pintype "unspecified"))
    )
    (net (code "2") (name "+5V") (class "Default")
      (node (ref "C1") (pin "1") (pinfunction "1_1") (pintype "input"))
      (node (ref "C10") (pin "1") (pinfunction "1_1") (pintype "input"))
      (node (ref "C13") (pin "2") (pinfunction "2_2") (pintype "unspecified"))
      (node (ref "C2") (pin "1") (pinfunction "1_1") (pintype "unspecified"))
      (node (ref "C3") (pin "1") (pinfunction "1_1") (pintype "unspecified"))
      (node (ref "C7") (pin "2") (pinfunction "2_2") (pintype "unspecified"))
      (node (ref "C8") (pin "1") (pinfunction "1_1") (pintype "unspecified"))
      (node (ref "D1") (pin "6") (pinfunction "IO_6") (pintype "unspecified"))
      (node (ref "H1") (pin "3") (pinfunction "3_3") (pintype "unspecified"))
      (node (ref "L2") (pin "1") (pinfunction "1_1") (pintype "unspecified"))
      (node (ref "R31") (pin "1") (pinfunction "1_1") (pintype "input"))
      (node (ref "R6") (pin "1") (pinfunction "1_1") (pintype "input"))
      (node (ref "U16") (pin "8") (pinfunction "VCC_8") (pintype "unspecified"))
      (node (ref "U24") (pin "4") (pinfunction "FEEDBACK_4") (pintype "unspecified"))
      (node (ref "U32") (pin "4") (pinfunction "4_4") (pintype "unspecified"))
      (node (ref "U34") (pin "6") (pinfunction "6_6") (pintype "unspecified"))
      (node (ref "U36") (pin "2") (pinfunction "VCC_2") (pintype "unspecified"))
      (node (ref "USB2") (pin "1") (pinfunction "VBUS_1") (pintype "unspecified"))
    )
    (net (code "3") (name "+12V") (class "Default")
      (node (ref "BUZZER1") (pin "2") (pinfunction "+_2") (pintype "unspecified"))
      (node (ref "C5") (pin "1") (pinfunction "1_1") (pintype "input"))
      (node (ref "C6") (pin "2") (pinfunction "2_2") (pintype "unspecified"))
      (node (ref "D4") (pin "2") (pinfunction "A_2") (pintype "unspecified"))
      (node (ref "D5") (pin "2") (pinfunction "A_2") (pintype "unspecified"))
      (node (ref "U10") (pin "1") (pinfunction "1_1") (pintype "unspecified"))
      (node (ref "U11") (pin "2") (pinfunction "2_2") (pintype "unspecified"))
      (node (ref "U13") (pin "2") (pinfunction "2_2") (pintype "unspecified"))
      (node (ref "U13") (pin "4") (pinfunction "4_4") (pintype "unspecified"))
      (node (ref "U13") (pin "6") (pinfunction "6_6") (pintype "unspecified"))
      (node (ref "U13") (pin "8") (pinfunction "8_8") (pintype "unspecified"))
      (node (ref "U15") (pin "2") (pinfunction "2_2") (pintype "unspecified"))
      (node (ref "U15") (pin "4") (pinfunction "4_4") (pintype "unspecified"))
      (node (ref "U15") (pin "6") (pinfunction "6_6") (pintype "unspecified"))
      (node (ref "U15") (pin "8") (pinfunction "8_8") (pintype "unspecified"))
      (node (ref "U19") (pin "1") (pinfunction "1_1") (pintype "unspecified"))
      (node (ref "U20") (pin "1") (pinfunction "1_1") (pintype "unspecified"))
      (node (ref "U3") (pin "1") (pinfunction "1_1") (pintype "unspecified"))
      (node (ref "U30") (pin "1") (pinfunction "1_1") (pintype "unspecified"))
      (node (ref "U34") (pin "7") (pinfunction "7_7") (pintype "unspecified"))
      (node (ref "U4") (pin "1") (pinfunction "1_1") (pintype "unspecified"))
      (node (ref "U7") (pin "1") (pinfunction "1_1") (pintype "unspecified"))
      (node (ref "U8") (pin "9") (pinfunction "VCOM_9") (pintype "unspecified"))
    )
    (net (code "4") (name "BUZZER") (class "Default")
      (node (ref "R27") (pin "2") (pinfunction "2_2") (pintype "input"))
      (node (ref "U2") (pin "15") (pinfunction "IO3_15") (pintype "unspecified"))
      (node (ref "U34") (pin "5") (pinfunction "5_5") (pintype "unspecified"))
      (node (ref "U8") (pin "7") (pinfunction "7B_7") (pintype "unspecified"))
    )
    (net (code "5") (name "ETH_IRQ") (class "Default")
      (node (ref "U2") (pin "39") (pinfunction "IO1_39") (pintype "unspecified"))
      (node (ref "W2") (pin "6") (pinfunction "INT_6") (pintype "unspecified"))
    )
    (net (code "6") (name "GND") (class "Default")
      (node (ref "B1") (pin "2") (pinfunction "2_2") (pintype "input"))
      (node (ref "BOOT") (pin "2") (pinfunction "2_2") (pintype "unspecified"))
      (node (ref "C1") (pin "2") (pinfunction "2_2") (pintype "input"))
      (node (ref "C10") (pin "2") (pinfunction "2_2") (pintype "input"))
      (node (ref "C12") (pin "2") (pinfunction "2_2") (pintype "unspecified"))
      (node (ref "C13") (pin "1") (pinfunction "1_1") (pintype "unspecified"))
      (node (ref "C14") (pin "1") (pinfunction "1_1") (pintype "unspecified"))
      (node (ref "C15") (pin "1") (pinfunction "1_1") (pintype "unspecified"))
      (node (ref "C16") (pin "1") (pinfunction "1_1") (pintype "unspecified"))
      (node (ref "C17") (pin "1") (pinfunction "1_1") (pintype "unspecified"))
      (node (ref "C18") (pin "1") (pinfunction "1_1") (pintype "unspecified"))
      (node (ref "C19") (pin "1") (pinfunction "1_1") (pintype "unspecified"))
      (node (ref "C2") (pin "2") (pinfunction "2_2") (pintype "unspecified"))
      (node (ref "C20") (pin "1") (pinfunction "1_1") (pintype "unspecified"))
      (node (ref "C21") (pin "1") (pinfunction "1_1") (pintype "unspecified"))
      (node (ref "C22") (pin "1") (pinfunction "1_1") (pintype "unspecified"))
      (node (ref "C23") (pin "1") (pinfunction "1_1") (pintype "unspecified"))
      (node (ref "C24") (pin "2") (pinfunction "2_2") (pintype "input"))
      (node (ref "C25") (pin "2") (pinfunction "2_2") (pintype "unspecified"))
      (node (ref "C28") (pin "2") (pinfunction "2_2") (pintype "unspecified"))
      (node (ref "C3") (pin "2") (pinfunction "2_2") (pintype "unspecified"))
      (node (ref "C30") (pin "2") (pinfunction "2_2") (pintype "input"))
      (node (ref "C4") (pin "2") (pinfunction "2_2") (pintype "input"))
      (node (ref "C5") (pin "2") (pinfunction "2_2") (pintype "input"))
      (node (ref "C6") (pin "1") (pinfunction "1_1") (pintype "unspecified"))
      (node (ref "C7") (pin "1") (pinfunction "1_1") (pintype "unspecified"))
      (node (ref "C8") (pin "2") (pinfunction "2_2") (pintype "unspecified"))
      (node (ref "C9") (pin "2") (pinfunction "2_2") (pintype "input"))
      (node (ref "D1") (pin "2") (pinfunction "VN_2") (pintype "unspecified"))
      (node (ref "D2") (pin "2") (pinfunction "A_2") (pintype "unspecified"))
      (node (ref "D3") (pin "2") (pinfunction "A_2") (pintype "unspecified"))
      (node (ref "H1") (pin "4") (pinfunction "4_4") (pintype "unspecified"))
      (node (ref "H2") (pin "6") (pinfunction "6_6") (pintype "input"))
      (node (ref "R21") (pin "1") (pinfunction "1_1") (pintype "input"))
      (node (ref "R22") (pin "1") (pinfunction "1_1") (pintype "input"))
      (node (ref "R23") (pin "1") (pinfunction "1_1") (pintype "input"))
      (node (ref "R24") (pin "1") (pinfunction "1_1") (pintype "input"))
      (node (ref "R25") (pin "1") (pinfunction "1_1") (pintype "input"))
      (node (ref "R26") (pin "1") (pinfunction "1_1") (pintype "input"))
      (node (ref "R27") (pin "1") (pinfunction "1_1") (pintype "input"))
      (node (ref "R33") (pin "1") (pinfunction "1_1") (pintype "input"))
      (node (ref "R5") (pin "2") (pinfunction "2_2") (pintype "input"))
      (node (ref "RESET") (pin "1") (pinfunction "1_1") (pintype "unspecified"))
      (node (ref "U1") (pin "6") (pinfunction "GND_6") (pintype "unspecified"))
      (node (ref "U11") (pin "1") (pinfunction "1_1") (pintype "unspecified"))
      (node (ref "U12") (pin "2") (pinfunction "CAT_2") (pintype "unspecified"))
      (node (ref "U12") (pin "4") (pinfunction "CAT_4") (pintype "unspecified"))
      (node (ref "U12") (pin "6") (pinfunction "CAT_6") (pintype "unspecified"))
      (node (ref "U12") (pin "8") (pinfunction "CAT_8") (pintype "unspecified"))
      (node (ref "U16") (pin "5") (pinfunction "GND_5") (pintype "unspecified"))
      (node (ref "U17") (pin "3") (pinfunction "GND_3") (pintype "unspecified"))
      (node (ref "U17") (pin "5") (pinfunction "ON/OFF_5") (pintype "unspecified"))
      (node (ref "U17") (pin "9") (pinfunction "EP_9") (pintype "unspecified"))
      (node (ref "U2") (pin "1") (pinfunction "GND_1") (pintype "passive"))
      (node (ref "U2") (pin "40") (pinfunction "GND_40") (pintype "passive"))
      (node (ref "U2") (pin "41") (pinfunction "GND_41") (pintype "passive"))
      (node (ref "U22") (pin "5") (pinfunction "GND_5") (pintype "passive"))
      (node (ref "U24") (pin "3") (pinfunction "GND_3") (pintype "unspecified"))
      (node (ref "U24") (pin "5") (pinfunction "ON/OFF_5") (pintype "unspecified"))
      (node (ref "U24") (pin "9") (pinfunction "PAD_9") (pintype "unspecified"))
      (node (ref "U29") (pin "2") (pinfunction "CAT_2") (pintype "unspecified"))
      (node (ref "U29") (pin "4") (pinfunction "CAT_4") (pintype "unspecified"))
      (node (ref "U29") (pin "6") (pinfunction "CAT_6") (pintype "unspecified"))
      (node (ref "U29") (pin "8") (pinfunction "CAT_8") (pintype "unspecified"))
      (node (ref "U30") (pin "4") (pinfunction "4_4") (pintype "unspecified"))
      (node (ref "U32") (pin "1") (pinfunction "1_1") (pintype "unspecified"))
      (node (ref "U34") (pin "8") (pinfunction "8_8") (pintype "unspecified"))
      (node (ref "U36") (pin "6") (pinfunction "GND_6") (pintype "unspecified"))
      (node (ref "U8") (pin "8") (pinfunction "E_8") (pintype "unspecified"))
      (node (ref "USB2") (pin "5") (pinfunction "GND_5") (pintype "unspecified"))
      (node (ref "W2") (pin "1") (pinfunction "GND_1") (pintype "unspecified"))
      (node (ref "W2") (pin "12") (pinfunction "GND_12") (pintype "unspecified"))
      (node (ref "W2") (pin "2") (pinfunction "GND_2") (pintype "unspecified"))
    )
    (net (code "7") (name "I2C_SCL") (class "Default")
      (node (ref "H1") (pin "1") (pinfunction "1_1") (pintype "unspecified"))
      (node (ref "R30") (pin "2") (pinfunction "2_2") (pintype "input"))
      (node (ref "U2") (pin "17") (pinfunction "IO9_17") (pintype "unspecified"))
      (node (ref "U22") (pin "8") (pinfunction "SCL_8") (pintype "unspecified"))
      (node (ref "U30") (pin "3") (pinfunction "3_3") (pintype "unspecified"))
    )
    (net (code "8") (name "I2C_SDA") (class "Default")
      (node (ref "H1") (pin "2") (pinfunction "2_2") (pintype "unspecified"))
      (node (ref "R14") (pin "2") (pinfunction "2_2") (pintype "input"))
      (node (ref "U2") (pin "12") (pinfunction "IO8_12") (pintype "unspecified"))
      (node (ref "U22") (pin "7") (pinfunction "SDA_7") (pintype "bidirectional"))
      (node (ref "U30") (pin "2") (pinfunction "2_2") (pintype "unspecified"))
    )
    (net (code "9") (name "IN_1") (class "Default")
      (node (ref "C15") (pin "2") (pinfunction "2_2") (pintype "unspecified"))
      (node (ref "U2") (pin "29") (pinfunction "IO36_29") (pintype "unspecified"))
      (node (ref "U29") (pin "15") (pinfunction "EM_15") (pintype "unspecified"))
    )
    (net (code "10") (name "IN_2") (class "Default")
      (node (ref "C16") (pin "2") (pinfunction "2_2") (pintype "unspecified"))
      (node (ref "U2") (pin "30") (pinfunction "IO37_30") (pintype "unspecified"))
      (node (ref "U29") (pin "13") (pinfunction "EM_13") (pintype "unspecified"))
    )
    (net (code "11") (name "IN_3") (class "Default")
      (node (ref "C17") (pin "2") (pinfunction "2_2") (pintype "unspecified"))
      (node (ref "U2") (pin "32") (pinfunction "IO39_32") (pintype "unspecified"))
      (node (ref "U29") (pin "11") (pinfunction "EM_11") (pintype "unspecified"))
    )
    (net (code "12") (name "IN_4") (class "Default")
      (node (ref "C18") (pin "2") (pinfunction "2_2") (pintype "unspecified"))
      (node (ref "U2") (pin "33") (pinfunction "IO40_33") (pintype "unspecified"))
      (node (ref "U29") (pin "9") (pinfunction "EM_9") (pintype "unspecified"))
    )
    (net (code "13") (name "IN_5") (class "Default")
      (node (ref "C19") (pin "2") (pinfunction "2_2") (pintype "unspecified"))
      (node (ref "U12") (pin "15") (pinfunction "EM_15") (pintype "unspecified"))
      (node (ref "U2") (pin "34") (pinfunction "IO41_34") (pintype "unspecified"))
    )
    (net (code "14") (name "IN_6") (class "Default")
      (node (ref "C20") (pin "2") (pinfunction "2_2") (pintype "unspecified"))
      (node (ref "U12") (pin "13") (pinfunction "EM_13") (pintype "unspecified"))
      (node (ref "U2") (pin "35") (pinfunction "IO42_35") (pintype "unspecified"))
    )
    (net (code "15") (name "IN_7") (class "Default")
      (node (ref "C21") (pin "2") (pinfunction "2_2") (pintype "unspecified"))
      (node (ref "U12") (pin "11") (pinfunction "EM_11") (pintype "unspecified"))
      (node (ref "U2") (pin "38") (pinfunction "IO2_38") (pintype "unspecified"))
    )
    (net (code "16") (name "IN_8") (class "Default")
      (node (ref "C22") (pin "2") (pinfunction "2_2") (pintype "unspecified"))
      (node (ref "U12") (pin "9") (pinfunction "EM_9") (pintype "unspecified"))
      (node (ref "U2") (pin "16") (pinfunction "IO46_16") (pintype "unspecified"))
    )
    (net (code "17") (name "LED_ALARM") (class "Default")
      (node (ref "R11") (pin "1") (pinfunction "1_1") (pintype "input"))
      (node (ref "U2") (pin "28") (pinfunction "IO35_28") (pintype "unspecified"))
    )
    (net (code "18") (name "LED_STATUS") (class "Default")
      (node (ref "R12") (pin "1") (pinfunction "1_1") (pintype "input"))
      (node (ref "R8") (pin "1") (pinfunction "1_1") (pintype "input"))
      (node (ref "U2") (pin "25") (pinfunction "IO48_25") (pintype "unspecified"))
    )
    (net (code "19") (name "LED_WIFI") (class "Default")
      (node (ref "R13") (pin "1") (pinfunction "1_1") (pintype "input"))
      (node (ref "U2") (pin "31") (pinfunction "IO38_31") (pintype "unspecified"))
    )
    (net (code "20") (name "MISO") (class "Default")
      (node (ref "U1") (pin "5") (pinfunction "MISO_5") (pintype "unspecified"))
      (node (ref "U2") (pin "20") (pinfunction "IO12_20") (pintype "unspecified"))
      (node (ref "W2") (pin "7") (pinfunction "MISO_7") (pintype "unspecified"))
    )
    (net (code "21") (name "MOSI") (class "Default")
      (node (ref "U1") (pin "3") (pinfunction "MOSI_3") (pintype "unspecified"))
      (node (ref "U2") (pin "19") (pinfunction "IO11_19") (pintype "unspecified"))
      (node (ref "W2") (pin "3") (pinfunction "MOSI_3") (pintype "unspecified"))
    )
    (net (code "22") (name "Net-(BUZZER1--)") (class "Default")
      (node (ref "BUZZER1") (pin "1") (pinfunction "-_1") (pintype "unspecified"))
      (node (ref "U8") (pin "10") (pinfunction "7C_10") (pintype "unspecified"))
    )
    (net (code "23") (name "Net-(D1-VP)") (class "Default")
      (node (ref "D1") (pin "5") (pinfunction "VP_5") (pintype "unspecified"))
      (node (ref "R31") (pin "2") (pinfunction "2_2") (pintype "input"))
    )
    (net (code "24") (name "Net-(D2-K)") (class "Default")
      (node (ref "D2") (pin "1") (pinfunction "K_1") (pintype "unspecified"))
      (node (ref "L2") (pin "2") (pinfunction "2_2") (pintype "unspecified"))
      (node (ref "U24") (pin "2") (pinfunction "VOUT_2") (pintype "unspecified"))
    )
    (net (code "25") (name "Net-(D3-K)") (class "Default")
      (node (ref "D3") (pin "1") (pinfunction "K_1") (pintype "unspecified"))
      (node (ref "L1") (pin "2") (pinfunction "2_2") (pintype "unspecified"))
      (node (ref "U17") (pin "2") (pinfunction "VOUT_2") (pintype "unspecified"))
    )
    (net (code "26") (name "Net-(D4-K)") (class "Default")
      (node (ref "C12") (pin "1") (pinfunction "1_1") (pintype "unspecified"))
      (node (ref "C24") (pin "1") (pinfunction "1_1") (pintype "input"))
      (node (ref "D4") (pin "1") (pinfunction "K_1") (pintype "unspecified"))
      (node (ref "U24") (pin "1") (pinfunction "VIN_1") (pintype "unspecified"))
    )
    (net (code "27") (name "Net-(D5-K)") (class "Default")
      (node (ref "C25") (pin "1") (pinfunction "1_1") (pintype "unspecified"))
      (node (ref "C4") (pin "1") (pinfunction "1_1") (pintype "input"))
      (node (ref "D5") (pin "1") (pinfunction "K_1") (pintype "unspecified"))
      (node (ref "U17") (pin "1") (pinfunction "VIN_1") (pintype "unspecified"))
    )
    (net (code "28") (name "Net-(H2-Pad2)") (class "Default")
      (node (ref "H2") (pin "2") (pinfunction "2_2") (pintype "input"))
      (node (ref "R13") (pin "2") (pinfunction "2_2") (pintype "input"))
    )
    (net (code "29") (name "Net-(H2-Pad3)") (class "Default")
      (node (ref "H2") (pin "3") (pinfunction "3_3") (pintype "input"))
      (node (ref "R12") (pin "2") (pinfunction "2_2") (pintype "input"))
    )
    (net (code "30") (name "Net-(H2-Pad4)") (class "Default")
      (node (ref "H2") (pin "4") (pinfunction "4_4") (pintype "input"))
      (node (ref "R11") (pin "2") (pinfunction "2_2") (pintype "input"))
    )
    (net (code "31") (name "Net-(H2-Pad5)") (class "Default")
      (node (ref "H2") (pin "5") (pinfunction "5_5") (pintype "input"))
      (node (ref "R2") (pin "2") (pinfunction "2_2") (pintype "input"))
    )
    (net (code "32") (name "Net-(R8-Pad2)") (class "Default")
      (node (ref "R8") (pin "2") (pinfunction "2_2") (pintype "input"))
      (node (ref "U34") (pin "4") (pinfunction "4_4") (pintype "unspecified"))
    )
    (net (code "33") (name "Net-(R9-Pad1)") (class "Default")
      (node (ref "R9") (pin "1") (pinfunction "1_1") (pintype "input"))
      (node (ref "U15") (pin "1") (pinfunction "1_1") (pintype "unspecified"))
    )
    (net (code "34") (name "Net-(R9-Pad2)") (class "Default")
      (node (ref "R9") (pin "2") (pinfunction "2_2") (pintype "input"))
      (node (ref "U29") (pin "1") (pinfunction "AN_1") (pintype "unspecified"))
    )
    (net (code "35") (name "Net-(R10-Pad1)") (class "Default")
      (node (ref "R10") (pin "1") (pinfunction "1_1") (pintype "input"))
      (node (ref "U15") (pin "3") (pinfunction "3_3") (pintype "unspecified"))
    )
    (net (code "36") (name "Net-(R10-Pad2)") (class "Default")
      (node (ref "R10") (pin "2") (pinfunction "2_2") (pintype "input"))
      (node (ref "U29") (pin "3") (pinfunction "AN_3") (pintype "unspecified"))
    )
    (net (code "37") (name "Net-(R15-Pad1)") (class "Default")
      (node (ref "R15") (pin "1") (pinfunction "1_1") (pintype "input"))
      (node (ref "U15") (pin "5") (pinfunction "5_5") (pintype "unspecified"))
    )
    (net (code "38") (name "Net-(R15-Pad2)") (class "Default")
      (node (ref "R15") (pin "2") (pinfunction "2_2") (pintype "input"))
      (node (ref "U29") (pin "5") (pinfunction "AN_5") (pintype "unspecified"))
    )
    (net (code "39") (name "Net-(R16-Pad1)") (class "Default")
      (node (ref "R16") (pin "1") (pinfunction "1_1") (pintype "input"))
      (node (ref "U15") (pin "7") (pinfunction "7_7") (pintype "unspecified"))
    )
    (net (code "40") (name "Net-(R16-Pad2)") (class "Default")
      (node (ref "R16") (pin "2") (pinfunction "2_2") (pintype "input"))
      (node (ref "U29") (pin "7") (pinfunction "AN_7") (pintype "unspecified"))
    )
    (net (code "41") (name "Net-(R17-Pad1)") (class "Default")
      (node (ref "R17") (pin "1") (pinfunction "1_1") (pintype "input"))
      (node (ref "U13") (pin "7") (pinfunction "7_7") (pintype "unspecified"))
    )
    (net (code "42") (name "Net-(R17-Pad2)") (class "Default")
      (node (ref "R17") (pin "2") (pinfunction "2_2") (pintype "input"))
      (node (ref "U12") (pin "7") (pinfunction "AN_7") (pintype "unspecified"))
    )
    (net (code "43") (name "Net-(R18-Pad1)") (class "Default")
      (node (ref "R18") (pin "1") (pinfunction "1_1") (pintype "input"))
      (node (ref "U13") (pin "5") (pinfunction "5_5") (pintype "unspecified"))
    )
    (net (code "44") (name "Net-(R18-Pad2)") (class "Default")
      (node (ref "R18") (pin "2") (pinfunction "2_2") (pintype "input"))
      (node (ref "U12") (pin "5") (pinfunction "AN_5") (pintype "unspecified"))
    )
    (net (code "45") (name "Net-(R19-Pad1)") (class "Default")
      (node (ref "R19") (pin "1") (pinfunction "1_1") (pintype "input"))
      (node (ref "U13") (pin "3") (pinfunction "3_3") (pintype "unspecified"))
    )
    (net (code "46") (name "Net-(R19-Pad2)") (class "Default")
      (node (ref "R19") (pin "2") (pinfunction "2_2") (pintype "input"))
      (node (ref "U12") (pin "3") (pinfunction "AN_3") (pintype "unspecified"))
    )
    (net (code "47") (name "Net-(R20-Pad1)") (class "Default")
      (node (ref "R20") (pin "1") (pinfunction "1_1") (pintype "input"))
      (node (ref "U13") (pin "1") (pinfunction "1_1") (pintype "unspecified"))
    )
    (net (code "48") (name "Net-(R20-Pad2)") (class "Default")
      (node (ref "R20") (pin "2") (pinfunction "2_2") (pintype "input"))
      (node (ref "U12") (pin "1") (pinfunction "AN_1") (pintype "unspecified"))
    )
    (net (code "49") (name "Net-(U2-EN)") (class "Default")
      (node (ref "R1") (pin "1") (pinfunction "1_1") (pintype "input"))
      (node (ref "RESET") (pin "2") (pinfunction "2_2") (pintype "unspecified"))
      (node (ref "U2") (pin "3") (pinfunction "EN_3") (pintype "unspecified"))
    )
    (net (code "50") (name "Net-(U2-IO0)") (class "Default")
      (node (ref "BOOT") (pin "1") (pinfunction "1_1") (pintype "unspecified"))
      (node (ref "R34") (pin "1") (pinfunction "1_1") (pintype "input"))
      (node (ref "U2") (pin "27") (pinfunction "IO0_27") (pintype "unspecified"))
    )
    (net (code "51") (name "Net-(U3-Pad3)") (class "Default")
      (node (ref "U3") (pin "3") (pinfunction "3_3") (pintype "unspecified"))
      (node (ref "U5") (pin "2") (pinfunction "2_2") (pintype "unspecified"))
    )
    (net (code "52") (name "Net-(U3-Pad4)") (class "Default")
      (node (ref "U3") (pin "4") (pinfunction "4_4") (pintype "unspecified"))
      (node (ref "U5") (pin "1") (pinfunction "1_1") (pintype "unspecified"))
    )
    (net (code "53") (name "Net-(U4-Pad3)") (class "Default")
      (node (ref "U4") (pin "3") (pinfunction "3_3") (pintype "unspecified"))
      (node (ref "U6") (pin "2") (pinfunction "2_2") (pintype "unspecified"))
    )
    (net (code "54") (name "Net-(U4-Pad4)") (class "Default")
      (node (ref "U4") (pin "4") (pinfunction "4_4") (pintype "unspecified"))
      (node (ref "U6") (pin "1") (pinfunction "1_1") (pintype "unspecified"))
    )
    (net (code "55") (name "Net-(U8-1C)") (class "Default")
      (node (ref "U4") (pin "2") (pinfunction "2_2") (pintype "unspecified"))
      (node (ref "U8") (pin "16") (pinfunction "1C_16") (pintype "unspecified"))
    )
    (net (code "56") (name "Net-(U8-2C)") (class "Default")
      (node (ref "U3") (pin "2") (pinfunction "2_2") (pintype "unspecified"))
      (node (ref "U8") (pin "15") (pinfunction "2C_15") (pintype "unspecified"))
    )
    (net (code "57") (name "Net-(U8-3C)") (class "Default")
      (node (ref "U7") (pin "2") (pinfunction "2_2") (pintype "unspecified"))
      (node (ref "U8") (pin "14") (pinfunction "3C_14") (pintype "unspecified"))
    )
    (net (code "58") (name "Net-(U8-4C)") (class "Default")
      (node (ref "U20") (pin "2") (pinfunction "2_2") (pintype "unspecified"))
      (node (ref "U8") (pin "13") (pinfunction "4C_13") (pintype "unspecified"))
    )
    (net (code "59") (name "Net-(U8-5C)") (class "Default")
      (node (ref "U19") (pin "2") (pinfunction "2_2") (pintype "unspecified"))
      (node (ref "U8") (pin "12") (pinfunction "5C_12") (pintype "unspecified"))
    )
    (net (code "60") (name "Net-(U8-6C)") (class "Default")
      (node (ref "U10") (pin "2") (pinfunction "2_2") (pintype "unspecified"))
      (node (ref "U8") (pin "11") (pinfunction "6C_11") (pintype "unspecified"))
    )
    (net (code "61") (name "Net-(U10-Pad3)") (class "Default")
      (node (ref "U10") (pin "3") (pinfunction "3_3") (pintype "unspecified"))
      (node (ref "U9") (pin "2") (pinfunction "2_2") (pintype "unspecified"))
    )
    (net (code "62") (name "Net-(U10-Pad4)") (class "Default")
      (node (ref "U10") (pin "4") (pinfunction "4_4") (pintype "unspecified"))
      (node (ref "U9") (pin "1") (pinfunction "1_1") (pintype "unspecified"))
    )
    (net (code "63") (name "Net-(U14-Pad1)") (class "Default")
      (node (ref "U14") (pin "1") (pinfunction "1_1") (pintype "unspecified"))
      (node (ref "U7") (pin "4") (pinfunction "4_4") (pintype "unspecified"))
    )
    (net (code "64") (name "Net-(U14-Pad2)") (class "Default")
      (node (ref "U14") (pin "2") (pinfunction "2_2") (pintype "unspecified"))
      (node (ref "U7") (pin "3") (pinfunction "3_3") (pintype "unspecified"))
    )
    (net (code "65") (name "Net-(U16-A)") (class "Default")
      (node (ref "R6") (pin "2") (pinfunction "2_2") (pintype "input"))
      (node (ref "R7") (pin "1") (pinfunction "1_1") (pintype "unspecified"))
      (node (ref "U16") (pin "6") (pinfunction "A_6") (pintype "unspecified"))
      (node (ref "U32") (pin "2") (pinfunction "2_2") (pintype "unspecified"))
    )
    (net (code "66") (name "Net-(U16-B)") (class "Default")
      (node (ref "R5") (pin "1") (pinfunction "1_1") (pintype "input"))
      (node (ref "R7") (pin "2") (pinfunction "2_2") (pintype "unspecified"))
      (node (ref "U16") (pin "7") (pinfunction "B_7") (pintype "unspecified"))
      (node (ref "U32") (pin "3") (pinfunction "3_3") (pintype "unspecified"))
    )
    (net (code "67") (name "Net-(U16-DE)") (class "Default")
      (node (ref "R4") (pin "2") (pinfunction "2_2") (pintype "input"))
      (node (ref "U16") (pin "2") (pinfunction "RE#_2") (pintype "unspecified"))
      (node (ref "U16") (pin "3") (pinfunction "DE_3") (pintype "unspecified"))
    )
    (net (code "68") (name "Net-(U17-FEEDBACK)") (class "Default")
      (node (ref "R32") (pin "1") (pinfunction "1_1") (pintype "input"))
      (node (ref "R33") (pin "2") (pinfunction "2_2") (pintype "input"))
      (node (ref "U17") (pin "4") (pinfunction "FEEDBACK_4") (pintype "unspecified"))
    )
    (net (code "69") (name "Net-(U18-Pad1)") (class "Default")
      (node (ref "U18") (pin "1") (pinfunction "1_1") (pintype "unspecified"))
      (node (ref "U19") (pin "4") (pinfunction "4_4") (pintype "unspecified"))
    )
    (net (code "70") (name "Net-(U18-Pad2)") (class "Default")
      (node (ref "U18") (pin "2") (pinfunction "2_2") (pintype "unspecified"))
      (node (ref "U19") (pin "3") (pinfunction "3_3") (pintype "unspecified"))
    )
    (net (code "71") (name "Net-(U20-Pad3)") (class "Default")
      (node (ref "U20") (pin "3") (pinfunction "3_3") (pintype "unspecified"))
      (node (ref "U21") (pin "2") (pinfunction "2_2") (pintype "unspecified"))
    )
    (net (code "72") (name "Net-(U20-Pad4)") (class "Default")
      (node (ref "U20") (pin "4") (pinfunction "4_4") (pintype "unspecified"))
      (node (ref "U21") (pin "1") (pinfunction "1_1") (pintype "unspecified"))
    )
    (net (code "73") (name "Net-(U22-VBAT)") (class "Default")
      (node (ref "B1") (pin "1") (pinfunction "1_1") (pintype "input"))
      (node (ref "U22") (pin "6") (pinfunction "VBAT_6") (pintype "passive"))
    )
    (net (code "74") (name "OW_1") (class "Default")
      (node (ref "D1") (pin "1") (pinfunction "IO_1") (pintype "unspecified"))
      (node (ref "R29") (pin "1") (pinfunction "1_1") (pintype "input"))
      (node (ref "U2") (pin "13") (pinfunction "IO19_13") (pintype "unspecified"))
      (node (ref "U34") (pin "2") (pinfunction "2_2") (pintype "unspecified"))
      (node (ref "USB2") (pin "2") (pinfunction "D-_2") (pintype "unspecified"))
    )
    (net (code "75") (name "OW_2") (class "Default")
      (node (ref "D1") (pin "3") (pinfunction "IO_3") (pintype "unspecified"))
      (node (ref "R28") (pin "1") (pinfunction "1_1") (pintype "input"))
      (node (ref "U2") (pin "14") (pinfunction "IO20_14") (pintype "unspecified"))
      (node (ref "U34") (pin "3") (pinfunction "3_3") (pintype "unspecified"))
      (node (ref "USB2") (pin "3") (pinfunction "D+_3") (pintype "unspecified"))
    )
    (net (code "76") (name "RLY_1") (class "Default")
      (node (ref "R21") (pin "2") (pinfunction "2_2") (pintype "input"))
      (node (ref "U2") (pin "4") (pinfunction "IO4_4") (pintype "unspecified"))
      (node (ref "U8") (pin "1") (pinfunction "1B_1") (pintype "unspecified"))
    )
    (net (code "77") (name "RLY_2") (class "Default")
      (node (ref "R22") (pin "2") (pinfunction "2_2") (pintype "input"))
      (node (ref "U2") (pin "5") (pinfunction "IO5_5") (pintype "unspecified"))
      (node (ref "U8") (pin "2") (pinfunction "2B_2") (pintype "unspecified"))
    )
    (net (code "78") (name "RLY_3") (class "Default")
      (node (ref "R23") (pin "2") (pinfunction "2_2") (pintype "input"))
      (node (ref "U2") (pin "6") (pinfunction "IO6_6") (pintype "unspecified"))
      (node (ref "U8") (pin "3") (pinfunction "3B_3") (pintype "unspecified"))
    )
    (net (code "79") (name "RLY_4") (class "Default")
      (node (ref "R24") (pin "2") (pinfunction "2_2") (pintype "input"))
      (node (ref "U2") (pin "7") (pinfunction "IO7_7") (pintype "unspecified"))
      (node (ref "U8") (pin "4") (pinfunction "4B_4") (pintype "unspecified"))
    )
    (net (code "80") (name "RLY_5") (class "Default")
      (node (ref "R25") (pin "2") (pinfunction "2_2") (pintype "input"))
      (node (ref "U2") (pin "8") (pinfunction "IO15_8") (pintype "unspecified"))
      (node (ref "U8") (pin "5") (pinfunction "5B_5") (pintype "unspecified"))
    )
    (net (code "81") (name "RLY_6") (class "Default")
      (node (ref "R26") (pin "2") (pinfunction "2_2") (pintype "input"))
      (node (ref "U2") (pin "9") (pinfunction "IO16_9") (pintype "unspecified"))
      (node (ref "U8") (pin "6") (pinfunction "6B_6") (pintype "unspecified"))
    )
    (net (code "82") (name "SCK") (class "Default")
      (node (ref "U1") (pin "4") (pinfunction "CLK_4") (pintype "unspecified"))
      (node (ref "U2") (pin "21") (pinfunction "IO13_21") (pintype "unspecified"))
      (node (ref "W2") (pin "4") (pinfunction "SCLK_4") (pintype "unspecified"))
    )
    (net (code "83") (name "SS") (class "Default")
      (node (ref "U1") (pin "2") (pinfunction "CS_2") (pintype "unspecified"))
      (node (ref "U2") (pin "18") (pinfunction "IO10_18") (pintype "unspecified"))
      (node (ref "W2") (pin "5") (pinfunction "CS_5") (pintype "unspecified"))
    )
    (net (code "84") (name "S_1") (class "Default")
      (node (ref "U34") (pin "1") (pinfunction "1_1") (pintype "unspecified"))
    )
    (net (code "85") (name "UART1_RX") (class "Default")
      (node (ref "U2") (pin "11") (pinfunction "IO18_11") (pintype "unspecified"))
      (node (ref "U36") (pin "4") (pinfunction "RXD_4") (pintype "unspecified"))
    )
    (net (code "86") (name "UART1_TX") (class "Default")
      (node (ref "U2") (pin "10") (pinfunction "IO17_10") (pintype "unspecified"))
      (node (ref "U36") (pin "5") (pinfunction "TXD_5") (pintype "unspecified"))
    )
    (net (code "87") (name "UART2_CTRL") (class "Default")
      (node (ref "R4") (pin "1") (pinfunction "1_1") (pintype "input"))
      (node (ref "U2") (pin "22") (pinfunction "IO14_22") (pintype "unspecified"))
    )
    (net (code "88") (name "UART2_RX") (class "Default")
      (node (ref "R3") (pin "1") (pinfunction "1_1") (pintype "input"))
      (node (ref "U16") (pin "1") (pinfunction "RO_1") (pintype "unspecified"))
      (node (ref "U2") (pin "24") (pinfunction "IO47_24") (pintype "unspecified"))
    )
    (net (code "89") (name "UART2_TX") (class "Default")
      (node (ref "U16") (pin "4") (pinfunction "DI_4") (pintype "unspecified"))
      (node (ref "U2") (pin "23") (pinfunction "IO21_23") (pintype "unspecified"))
    )
    (net (code "90") (name "unconnected-(D1-IO-Pad4)") (class "Default")
      (node (ref "D1") (pin "4") (pinfunction "IO_4") (pintype "unspecified+no_connect"))
    )
    (net (code "91") (name "unconnected-(H2-Pad1)") (class "Default")
      (node (ref "H2") (pin "1") (pinfunction "1_1") (pintype "input+no_connect"))
    )
    (net (code "92") (name "unconnected-(U2-IO45-Pad26)") (class "Default")
      (node (ref "U2") (pin "26") (pinfunction "IO45_26") (pintype "unspecified+no_connect"))
    )
    (net (code "93") (name "unconnected-(U2-RXD0-Pad36)") (class "Default")
      (node (ref "U2") (pin "36") (pinfunction "RXD0_36") (pintype "unspecified+no_connect"))
    )
    (net (code "94") (name "unconnected-(U2-TXD0-Pad37)") (class "Default")
      (node (ref "U2") (pin "37") (pinfunction "TXD0_37") (pintype "unspecified+no_connect"))
    )
    (net (code "95") (name "unconnected-(U17-NC-Pad6)") (class "Default")
      (node (ref "U17") (pin "6") (pinfunction "NC_6") (pintype "unspecified+no_connect"))
    )
    (net (code "96") (name "unconnected-(U17-NC-Pad7)") (class "Default")
      (node (ref "U17") (pin "7") (pinfunction "NC_7") (pintype "unspecified+no_connect"))
    )
    (net (code "97") (name "unconnected-(U17-NC-Pad8)") (class "Default")
      (node (ref "U17") (pin "8") (pinfunction "NC_8") (pintype "unspecified+no_connect"))
    )
    (net (code "98") (name "unconnected-(U22-32kHz-Pad1)") (class "Default")
      (node (ref "U22") (pin "1") (pinfunction "32kHz_1") (pintype "unspecified+no_connect"))
    )
    (net (code "99") (name "unconnected-(U22-INT#{slash}SQW-Pad3)") (class "Default")
      (node (ref "U22") (pin "3") (pinfunction "INT#/SQW_3") (pintype "bidirectional+no_connect"))
    )
    (net (code "100") (name "unconnected-(U24-NC-Pad6)") (class "Default")
      (node (ref "U24") (pin "6") (pinfunction "NC_6") (pintype "unspecified+no_connect"))
    )
    (net (code "101") (name "unconnected-(U24-NC-Pad7)") (class "Default")
      (node (ref "U24") (pin "7") (pinfunction "NC_7") (pintype "unspecified+no_connect"))
    )
    (net (code "102") (name "unconnected-(U24-NC-Pad8)") (class "Default")
      (node (ref "U24") (pin "8") (pinfunction "NC_8") (pintype "unspecified+no_connect"))
    )
    (net (code "103") (name "unconnected-(U36-DTR-Pad11)") (class "Default")
      (node (ref "U36") (pin "11") (pinfunction "DTR_11") (pintype "unspecified+no_connect"))
    )
    (net (code "104") (name "unconnected-(U36-MIC+-Pad10)") (class "Default")
      (node (ref "U36") (pin "10") (pinfunction "MIC+_10") (pintype "unspecified+no_connect"))
    )
    (net (code "105") (name "unconnected-(U36-MIC--Pad9)") (class "Default")
      (node (ref "U36") (pin "9") (pinfunction "MIC-_9") (pintype "unspecified+no_connect"))
    )
    (net (code "106") (name "unconnected-(U36-NET-Pad1)") (class "Default")
      (node (ref "U36") (pin "1") (pinfunction "NET_1") (pintype "unspecified+no_connect"))
    )
    (net (code "107") (name "unconnected-(U36-RING-Pad12)") (class "Default")
      (node (ref "U36") (pin "12") (pinfunction "RING_12") (pintype "unspecified+no_connect"))
    )
    (net (code "108") (name "unconnected-(U36-RST-Pad3)") (class "Default")
      (node (ref "U36") (pin "3") (pinfunction "RST_3") (pintype "unspecified+no_connect"))
    )
    (net (code "109") (name "unconnected-(U36-SPK+-Pad8)") (class "Default")
      (node (ref "U36") (pin "8") (pinfunction "SPK+_8") (pintype "unspecified+no_connect"))
    )
    (net (code "110") (name "unconnected-(U36-SPK--Pad7)") (class "Default")
      (node (ref "U36") (pin "7") (pinfunction "SPK-_7") (pintype "unspecified+no_connect"))
    )
    (net (code "111") (name "unconnected-(USB2-EP-Pad6)") (class "Default")
      (node (ref "USB2") (pin "6") (pinfunction "EP_6") (pintype "unspecified+no_connect"))
    )
    (net (code "112") (name "unconnected-(USB2-EP-Pad7)") (class "Default")
      (node (ref "USB2") (pin "7") (pinfunction "EP_7") (pintype "unspecified+no_connect"))
    )
    (net (code "113") (name "unconnected-(USB2-EP-Pad8)") (class "Default")
      (node (ref "USB2") (pin "8") (pinfunction "EP_8") (pintype "unspecified+no_connect"))
    )
    (net (code "114") (name "unconnected-(USB2-EP-Pad9)") (class "Default")
      (node (ref "USB2") (pin "9") (pinfunction "EP_9") (pintype "unspecified+no_connect"))
    )
    (net (code "115") (name "unconnected-(USB2-ID-Pad4)") (class "Default")
      (node (ref "USB2") (pin "4") (pinfunction "ID_4") (pintype "unspecified+no_connect"))
    )
    (net (code "116") (name "unconnected-(W2-NC-Pad9)") (class "Default")
      (node (ref "W2") (pin "9") (pinfunction "NC_9") (pintype "unspecified+no_connect"))
    )
    (net (code "117") (name "unconnected-(W2-RST-Pad8)") (class "Default")
      (node (ref "W2") (pin "8") (pinfunction "RST_8") (pintype "unspecified+no_connect"))
    )
  )
)
